# Control_module.net
KiCad netlist of a schematic drawn in EAGLE
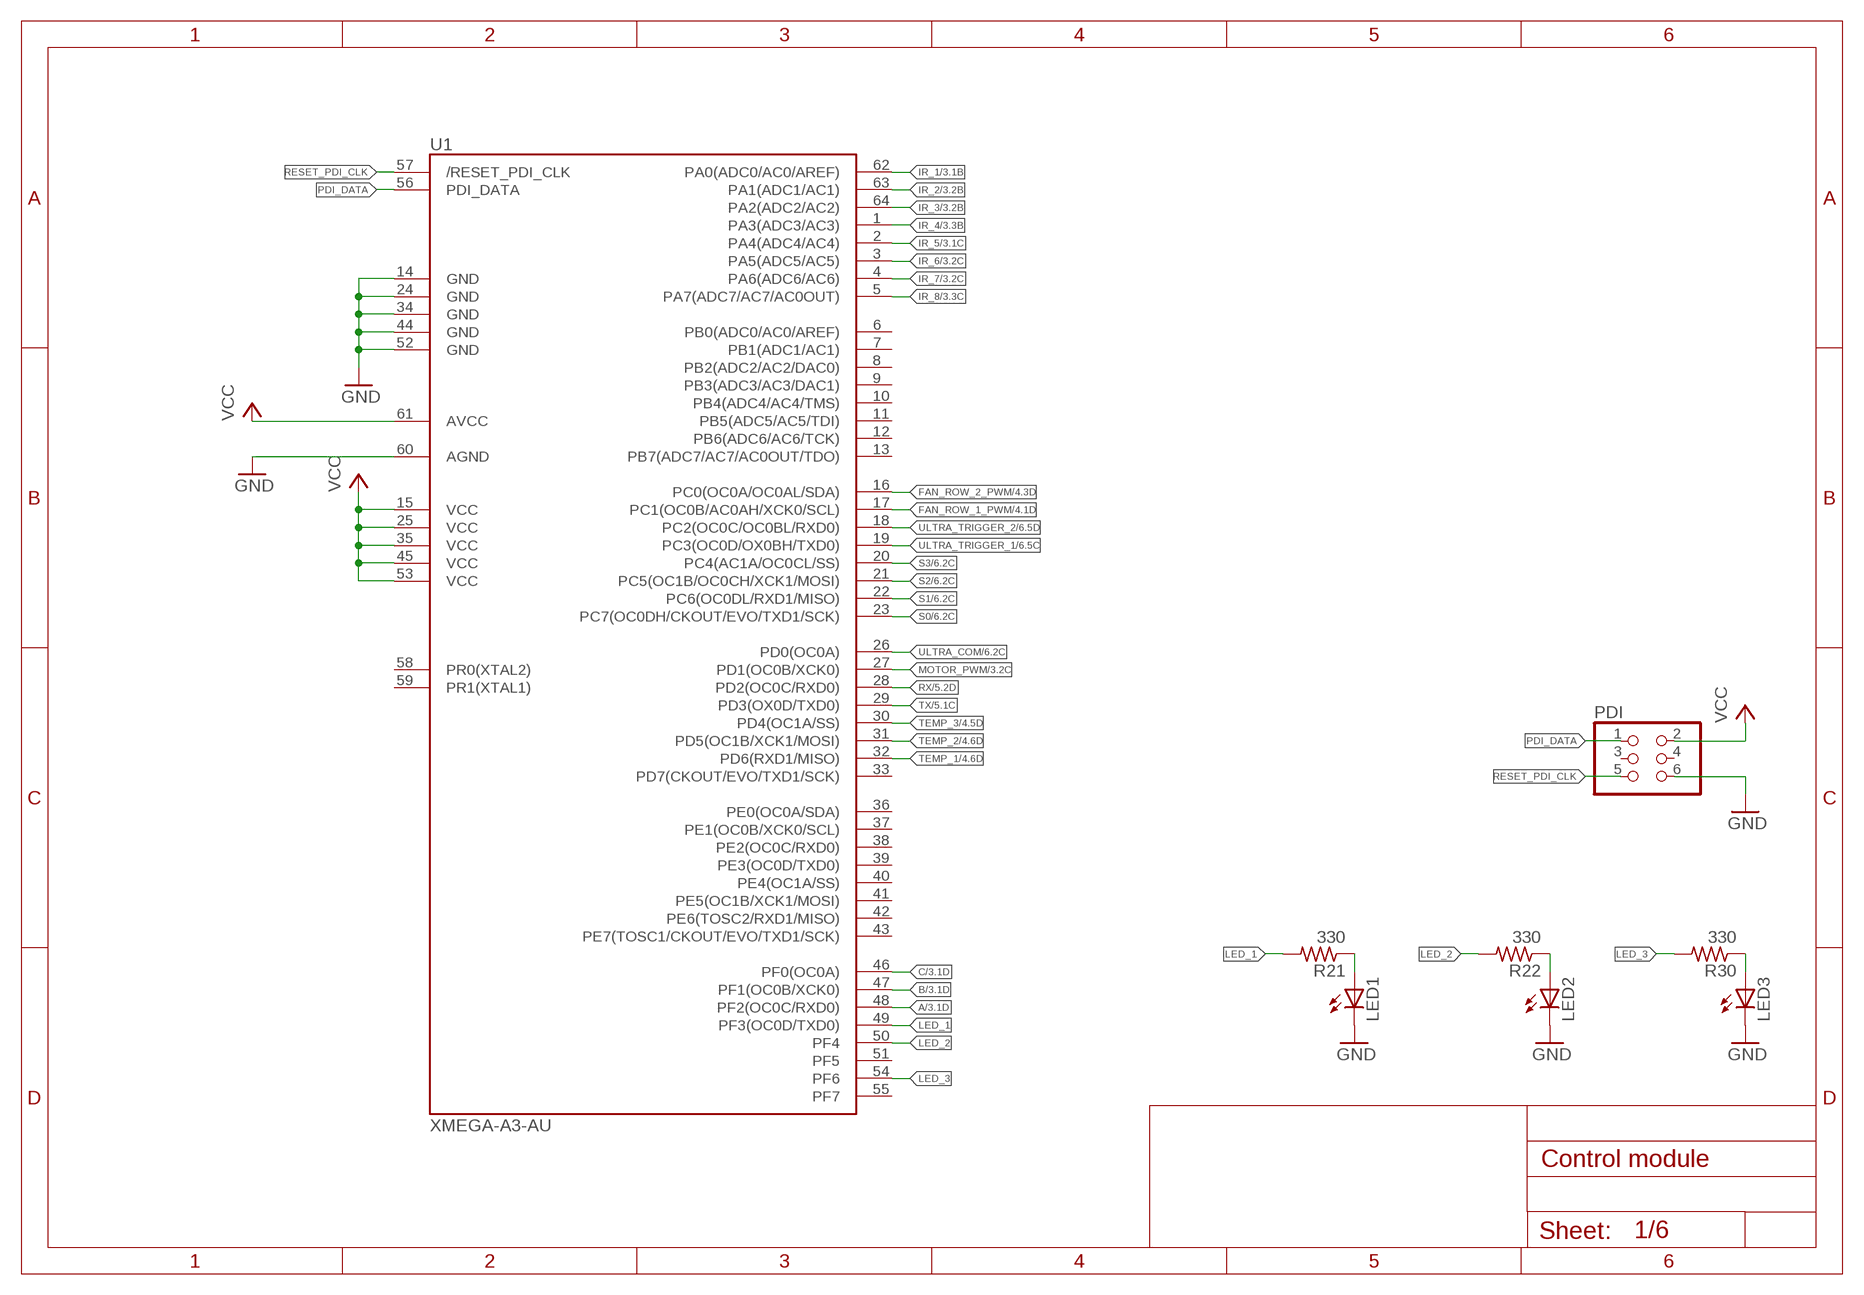
[diagram p0: schematic, sheet 1]
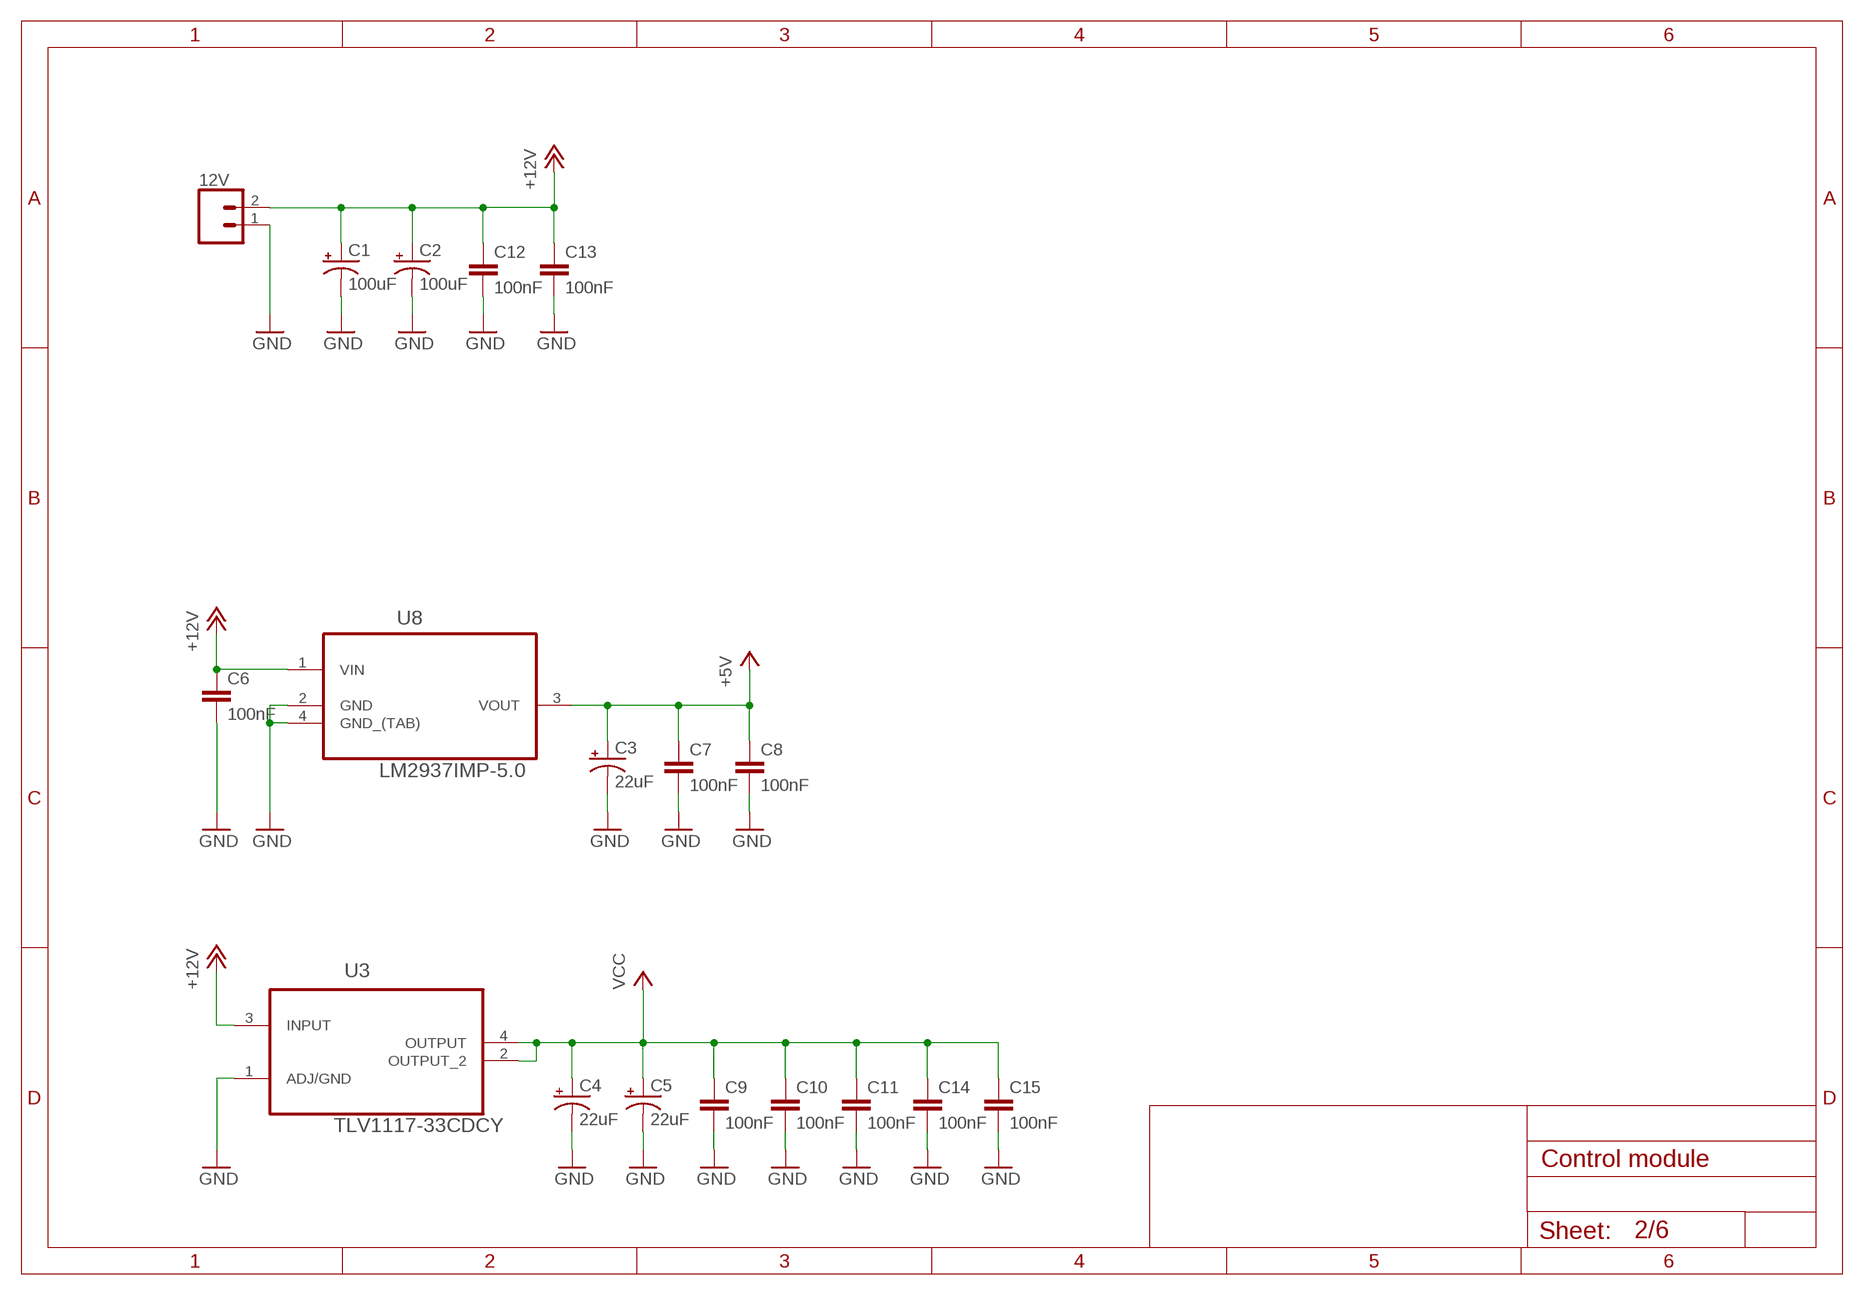
[diagram p1: schematic, sheet 2]
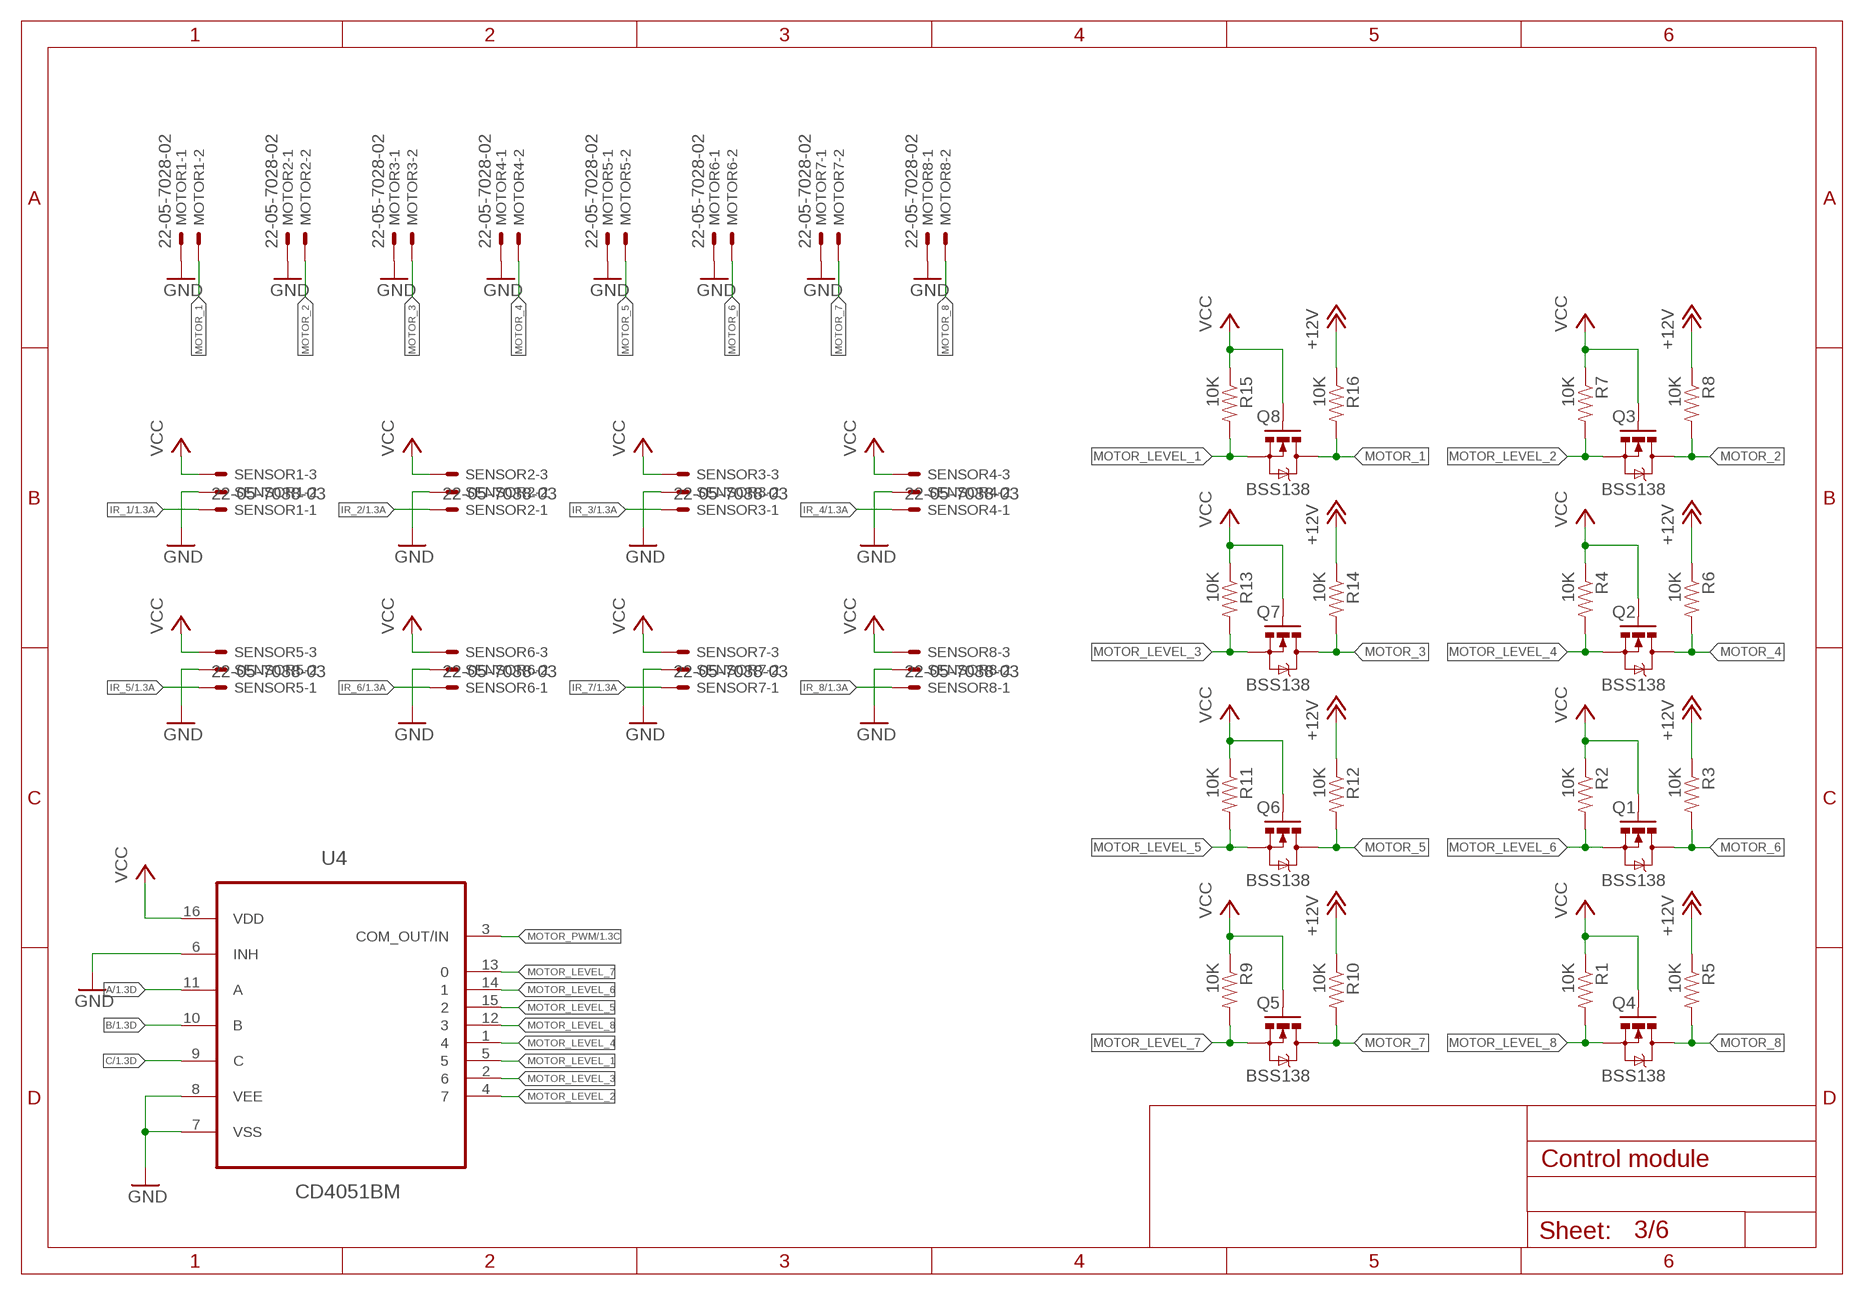
[diagram p2: schematic, sheet 3]
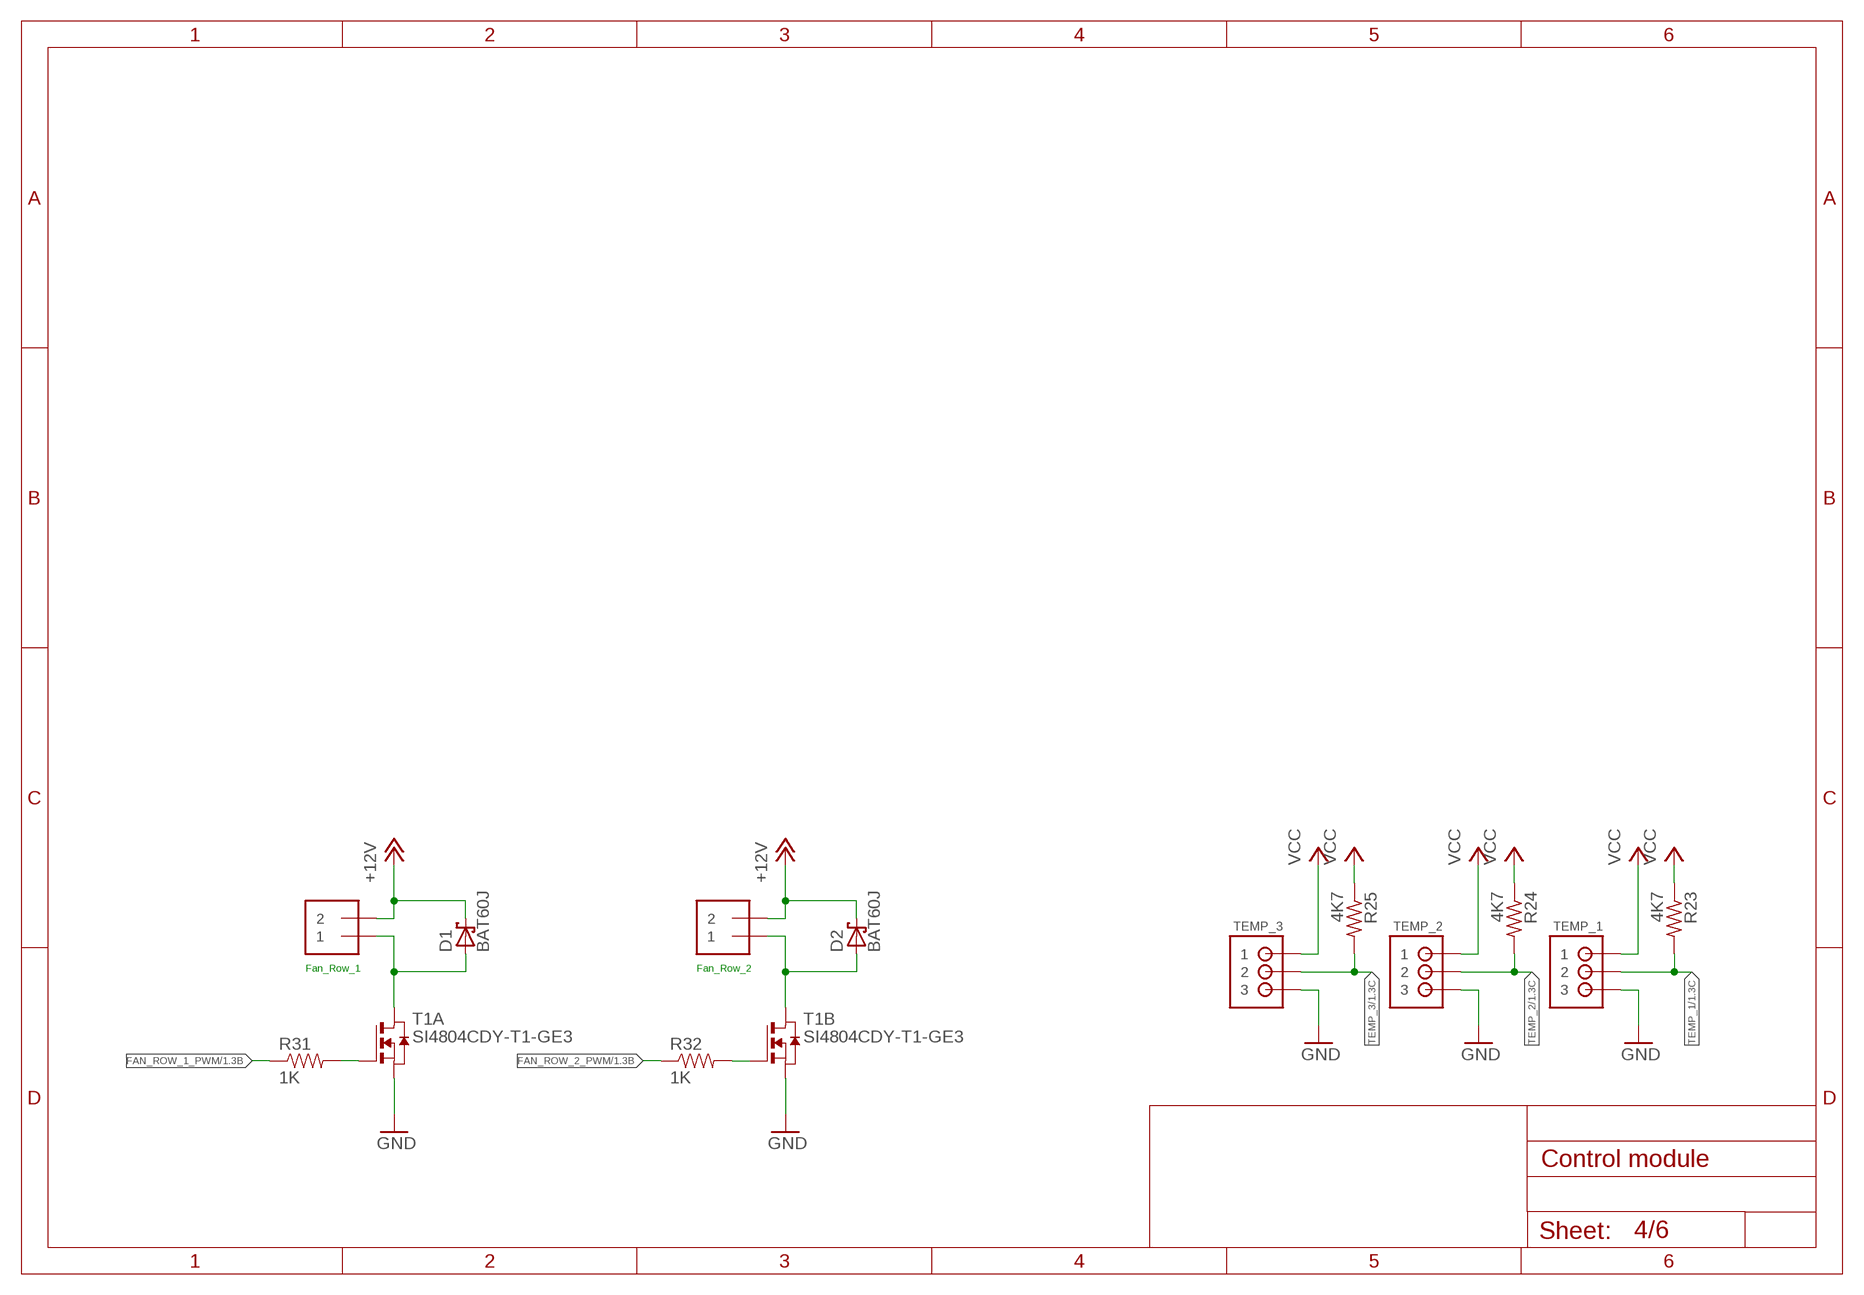
[diagram p3: schematic, sheet 4]
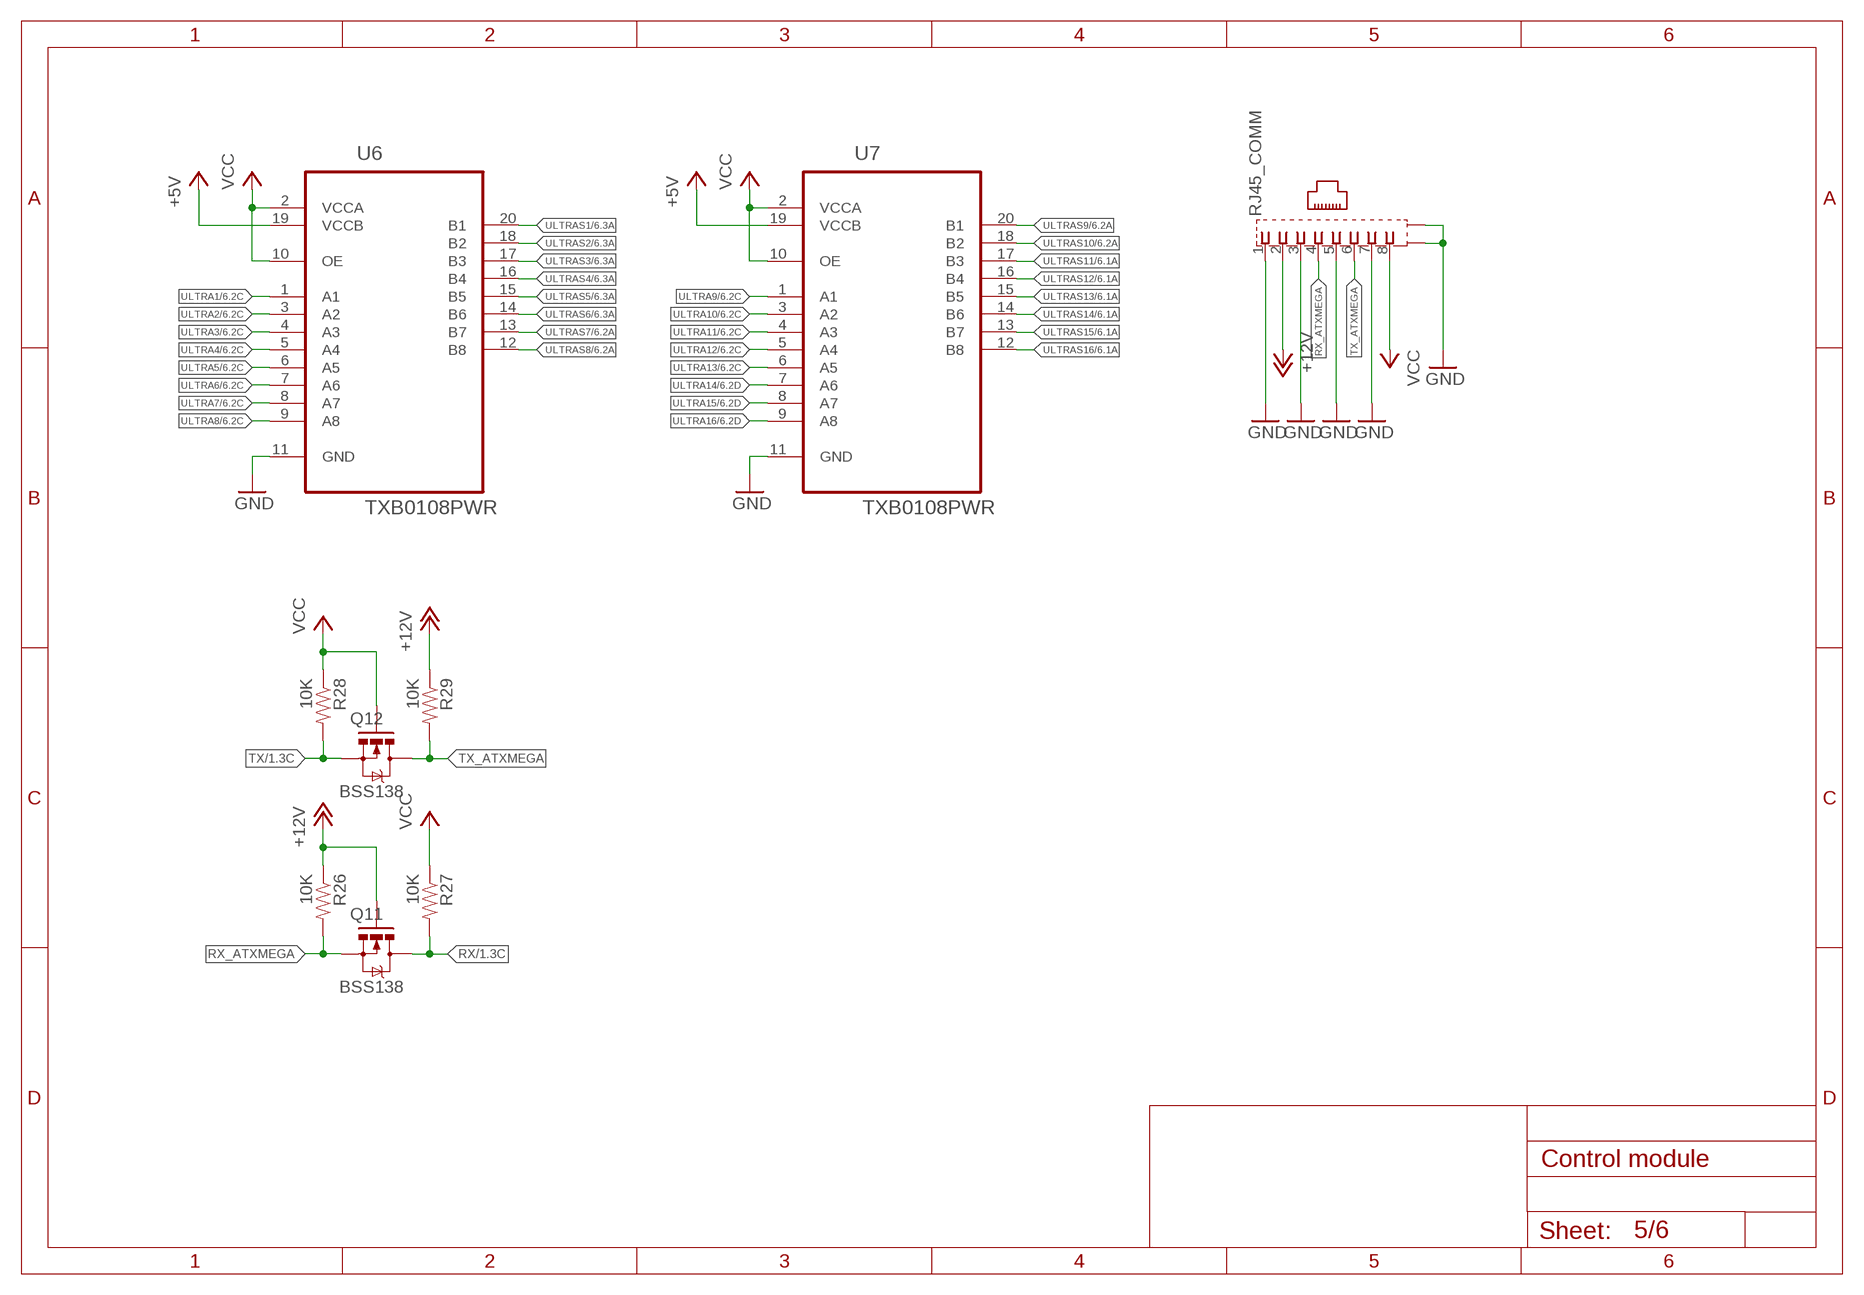
[diagram p4: schematic, sheet 5]
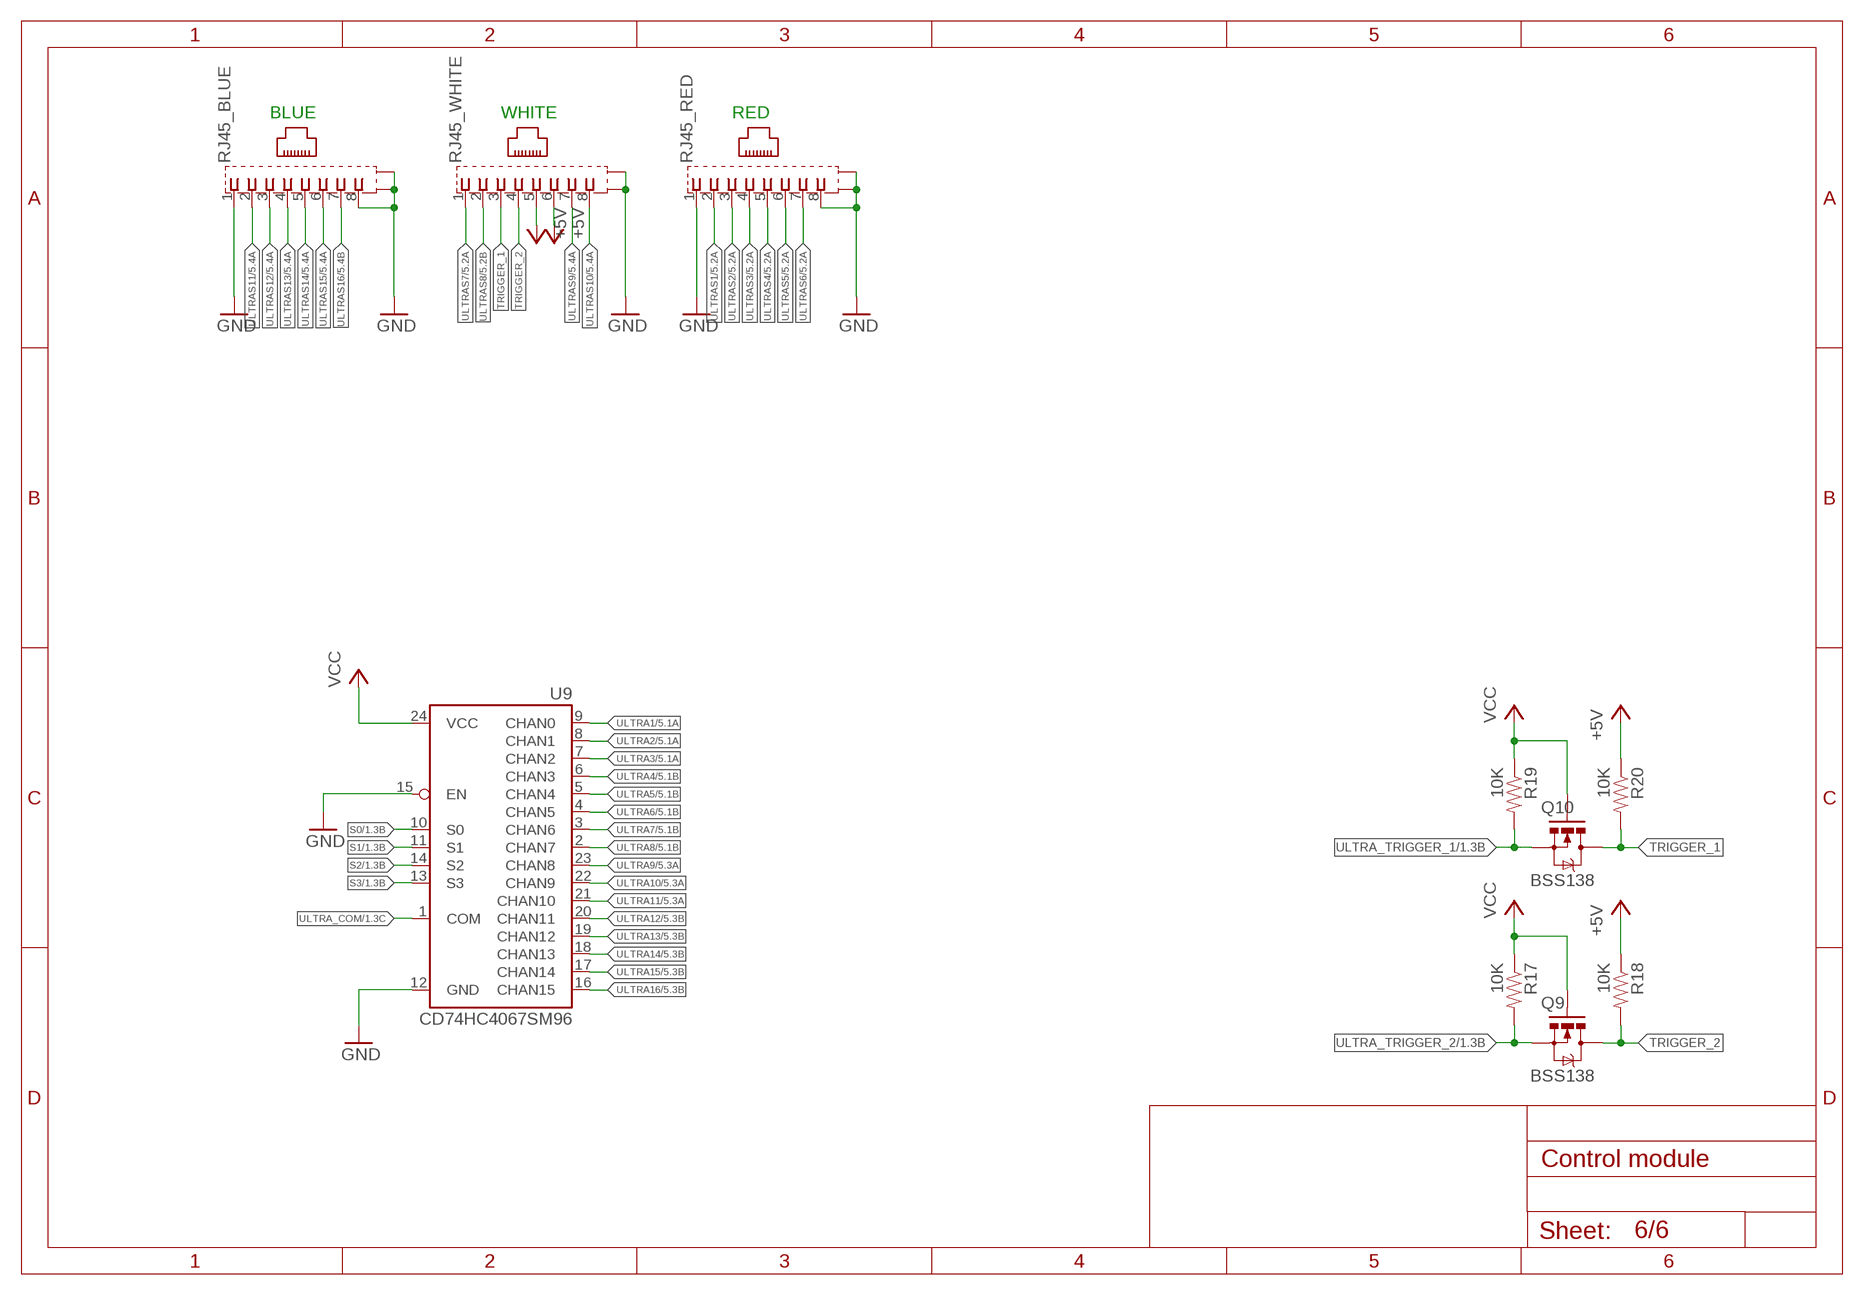
[diagram p5: schematic, sheet 6]

(export (version "E")
  (design (tool "Eeschema 10.0.6"))
  (components
    (comp (ref "MOTOR1")
      (value "22-05-7028-02")
      (footprint "eagle-import:7395-02")
      (fields (field (name "MF") "MOLEX"))
      (libsource (lib "eagle-import") (part "22-?-0205-7028"))
    )
    (comp (ref "MOTOR2")
      (value "22-05-7028-02")
      (footprint "eagle-import:7395-02")
      (fields (field (name "MF") "MOLEX"))
      (libsource (lib "eagle-import") (part "22-?-0205-7028"))
    )
    (comp (ref "MOTOR3")
      (value "22-05-7028-02")
      (footprint "eagle-import:7395-02")
      (fields (field (name "MF") "MOLEX"))
      (libsource (lib "eagle-import") (part "22-?-0205-7028"))
    )
    (comp (ref "MOTOR4")
      (value "22-05-7028-02")
      (footprint "eagle-import:7395-02")
      (fields (field (name "MF") "MOLEX"))
      (libsource (lib "eagle-import") (part "22-?-0205-7028"))
    )
    (comp (ref "MOTOR5")
      (value "22-05-7028-02")
      (footprint "eagle-import:7395-02")
      (fields (field (name "MF") "MOLEX"))
      (libsource (lib "eagle-import") (part "22-?-0205-7028"))
    )
    (comp (ref "MOTOR6")
      (value "22-05-7028-02")
      (footprint "eagle-import:7395-02")
      (fields (field (name "MF") "MOLEX"))
      (libsource (lib "eagle-import") (part "22-?-0205-7028"))
    )
    (comp (ref "MOTOR7")
      (value "22-05-7028-02")
      (footprint "eagle-import:7395-02")
      (fields (field (name "MF") "MOLEX"))
      (libsource (lib "eagle-import") (part "22-?-0205-7028"))
    )
    (comp (ref "MOTOR8")
      (value "22-05-7028-02")
      (footprint "eagle-import:7395-02")
      (fields (field (name "MF") "MOLEX"))
      (libsource (lib "eagle-import") (part "22-?-0205-7028"))
    )
    (comp (ref "Q1")
      (value "BSS138")
      (footprint "eagle-import:SOT23-3")
      (libsource (lib "eagle-import") (part "MOSFET-NCHANNELSMD"))
    )
    (comp (ref "Q2")
      (value "BSS138")
      (footprint "eagle-import:SOT23-3")
      (libsource (lib "eagle-import") (part "MOSFET-NCHANNELSMD"))
    )
    (comp (ref "Q3")
      (value "BSS138")
      (footprint "eagle-import:SOT23-3")
      (libsource (lib "eagle-import") (part "MOSFET-NCHANNELSMD"))
    )
    (comp (ref "Q4")
      (value "BSS138")
      (footprint "eagle-import:SOT23-3")
      (libsource (lib "eagle-import") (part "MOSFET-NCHANNELSMD"))
    )
    (comp (ref "Q5")
      (value "BSS138")
      (footprint "eagle-import:SOT23-3")
      (libsource (lib "eagle-import") (part "MOSFET-NCHANNELSMD"))
    )
    (comp (ref "Q6")
      (value "BSS138")
      (footprint "eagle-import:SOT23-3")
      (libsource (lib "eagle-import") (part "MOSFET-NCHANNELSMD"))
    )
    (comp (ref "Q7")
      (value "BSS138")
      (footprint "eagle-import:SOT23-3")
      (libsource (lib "eagle-import") (part "MOSFET-NCHANNELSMD"))
    )
    (comp (ref "Q8")
      (value "BSS138")
      (footprint "eagle-import:SOT23-3")
      (libsource (lib "eagle-import") (part "MOSFET-NCHANNELSMD"))
    )
    (comp (ref "R1")
      (value "10K")
      (footprint "eagle-import:0603-RES")
      (libsource (lib "eagle-import") (part "RESISTOR0603-RES"))
    )
    (comp (ref "R2")
      (value "10K")
      (footprint "eagle-import:0603-RES")
      (libsource (lib "eagle-import") (part "RESISTOR0603-RES"))
    )
    (comp (ref "R3")
      (value "10K")
      (footprint "eagle-import:0603-RES")
      (libsource (lib "eagle-import") (part "RESISTOR0603-RES"))
    )
    (comp (ref "R4")
      (value "10K")
      (footprint "eagle-import:0603-RES")
      (libsource (lib "eagle-import") (part "RESISTOR0603-RES"))
    )
    (comp (ref "R5")
      (value "10K")
      (footprint "eagle-import:0603-RES")
      (libsource (lib "eagle-import") (part "RESISTOR0603-RES"))
    )
    (comp (ref "R6")
      (value "10K")
      (footprint "eagle-import:0603-RES")
      (libsource (lib "eagle-import") (part "RESISTOR0603-RES"))
    )
    (comp (ref "R7")
      (value "10K")
      (footprint "eagle-import:0603-RES")
      (libsource (lib "eagle-import") (part "RESISTOR0603-RES"))
    )
    (comp (ref "R8")
      (value "10K")
      (footprint "eagle-import:0603-RES")
      (libsource (lib "eagle-import") (part "RESISTOR0603-RES"))
    )
    (comp (ref "R9")
      (value "10K")
      (footprint "eagle-import:0603-RES")
      (libsource (lib "eagle-import") (part "RESISTOR0603-RES"))
    )
    (comp (ref "R10")
      (value "10K")
      (footprint "eagle-import:0603-RES")
      (libsource (lib "eagle-import") (part "RESISTOR0603-RES"))
    )
    (comp (ref "R11")
      (value "10K")
      (footprint "eagle-import:0603-RES")
      (libsource (lib "eagle-import") (part "RESISTOR0603-RES"))
    )
    (comp (ref "R12")
      (value "10K")
      (footprint "eagle-import:0603-RES")
      (libsource (lib "eagle-import") (part "RESISTOR0603-RES"))
    )
    (comp (ref "R13")
      (value "10K")
      (footprint "eagle-import:0603-RES")
      (libsource (lib "eagle-import") (part "RESISTOR0603-RES"))
    )
    (comp (ref "R14")
      (value "10K")
      (footprint "eagle-import:0603-RES")
      (libsource (lib "eagle-import") (part "RESISTOR0603-RES"))
    )
    (comp (ref "R15")
      (value "10K")
      (footprint "eagle-import:0603-RES")
      (libsource (lib "eagle-import") (part "RESISTOR0603-RES"))
    )
    (comp (ref "R16")
      (value "10K")
      (footprint "eagle-import:0603-RES")
      (libsource (lib "eagle-import") (part "RESISTOR0603-RES"))
    )
    (comp (ref "SENSOR1")
      (value "22-05-7038-03")
      (footprint "eagle-import:7395-03")
      (fields (field (name "MF") "MOLEX"))
      (libsource (lib "eagle-import") (part "22-?-0305-7038"))
    )
    (comp (ref "SENSOR2")
      (value "22-05-7038-03")
      (footprint "eagle-import:7395-03")
      (fields (field (name "MF") "MOLEX"))
      (libsource (lib "eagle-import") (part "22-?-0305-7038"))
    )
    (comp (ref "SENSOR3")
      (value "22-05-7038-03")
      (footprint "eagle-import:7395-03")
      (fields (field (name "MF") "MOLEX"))
      (libsource (lib "eagle-import") (part "22-?-0305-7038"))
    )
    (comp (ref "SENSOR4")
      (value "22-05-7038-03")
      (footprint "eagle-import:7395-03")
      (fields (field (name "MF") "MOLEX"))
      (libsource (lib "eagle-import") (part "22-?-0305-7038"))
    )
    (comp (ref "SENSOR5")
      (value "22-05-7038-03")
      (footprint "eagle-import:7395-03")
      (fields (field (name "MF") "MOLEX"))
      (libsource (lib "eagle-import") (part "22-?-0305-7038"))
    )
    (comp (ref "SENSOR6")
      (value "22-05-7038-03")
      (footprint "eagle-import:7395-03")
      (fields (field (name "MF") "MOLEX"))
      (libsource (lib "eagle-import") (part "22-?-0305-7038"))
    )
    (comp (ref "SENSOR7")
      (value "22-05-7038-03")
      (footprint "eagle-import:7395-03")
      (fields (field (name "MF") "MOLEX"))
      (libsource (lib "eagle-import") (part "22-?-0305-7038"))
    )
    (comp (ref "SENSOR8")
      (value "22-05-7038-03")
      (footprint "eagle-import:7395-03")
      (fields (field (name "MF") "MOLEX"))
      (libsource (lib "eagle-import") (part "22-?-0305-7038"))
    )
    (comp (ref "U4")
      (value "CD4051BM")
      (footprint "eagle-import:SOIC127P600X175-16N")
      (libsource (lib "eagle-import") (part "CD4051BM"))
    )
    (comp (ref "LED1")
      (value "LEDCHIPLED_0805")
      (footprint "eagle-import:CHIPLED_0805")
      (libsource (lib "eagle-import") (part "LEDCHIPLED_0805"))
    )
    (comp (ref "LED2")
      (value "LEDCHIPLED_0805")
      (footprint "eagle-import:CHIPLED_0805")
      (libsource (lib "eagle-import") (part "LEDCHIPLED_0805"))
    )
    (comp (ref "LED3")
      (value "LEDCHIPLED_0805")
      (footprint "eagle-import:CHIPLED_0805")
      (libsource (lib "eagle-import") (part "LEDCHIPLED_0805"))
    )
    (comp (ref "PDI")
      (value "PINHD-2X3")
      (footprint "eagle-import:2X03")
      (libsource (lib "eagle-import") (part "PINHD-2X3"))
    )
    (comp (ref "R21")
      (value "330")
      (footprint "eagle-import:R0805")
      (libsource (lib "eagle-import") (part "adafruit_420_R-US_R0805"))
    )
    (comp (ref "R22")
      (value "330")
      (footprint "eagle-import:R0805")
      (libsource (lib "eagle-import") (part "adafruit_420_R-US_R0805"))
    )
    (comp (ref "R30")
      (value "330")
      (footprint "eagle-import:R0805")
      (libsource (lib "eagle-import") (part "adafruit_420_R-US_R0805"))
    )
    (comp (ref "U1")
      (value "XMEGA-A3-AU")
      (footprint "eagle-import:TQFP64_14X14MM_MCU")
      (libsource (lib "eagle-import") (part "XMEGA-A3-AU"))
    )
    (comp (ref "Q9")
      (value "BSS138")
      (footprint "eagle-import:SOT23-3")
      (libsource (lib "eagle-import") (part "MOSFET-NCHANNELSMD"))
    )
    (comp (ref "Q10")
      (value "BSS138")
      (footprint "eagle-import:SOT23-3")
      (libsource (lib "eagle-import") (part "MOSFET-NCHANNELSMD"))
    )
    (comp (ref "R17")
      (value "10K")
      (footprint "eagle-import:0603-RES")
      (libsource (lib "eagle-import") (part "RESISTOR0603-RES"))
    )
    (comp (ref "R18")
      (value "10K")
      (footprint "eagle-import:0603-RES")
      (libsource (lib "eagle-import") (part "RESISTOR0603-RES"))
    )
    (comp (ref "R19")
      (value "10K")
      (footprint "eagle-import:0603-RES")
      (libsource (lib "eagle-import") (part "RESISTOR0603-RES"))
    )
    (comp (ref "R20")
      (value "10K")
      (footprint "eagle-import:0603-RES")
      (libsource (lib "eagle-import") (part "RESISTOR0603-RES"))
    )
    (comp (ref "RJ45_BLUE")
      (value "0446200002")
      (footprint "eagle-import:0446200002")
      (fields (field (name "MF") "MOLEX"))
      (libsource (lib "eagle-import") (part "0446200002"))
    )
    (comp (ref "RJ45_RED")
      (value "0446200002")
      (footprint "eagle-import:0446200002")
      (fields (field (name "MF") "MOLEX"))
      (libsource (lib "eagle-import") (part "0446200002"))
    )
    (comp (ref "RJ45_WHITE")
      (value "0446200002")
      (footprint "eagle-import:0446200002")
      (fields (field (name "MF") "MOLEX"))
      (libsource (lib "eagle-import") (part "0446200002"))
    )
    (comp (ref "U9")
      (value "CD74HC4067SM96")
      (footprint "eagle-import:SSOP24")
      (libsource (lib "eagle-import") (part "744067SM96HC"))
    )
    (comp (ref "D1")
      (value "BAT60J")
      (footprint "eagle-import:SOD323_ST")
      (libsource (lib "eagle-import") (part "BAT60J"))
    )
    (comp (ref "D2")
      (value "BAT60J")
      (footprint "eagle-import:SOD323_ST")
      (libsource (lib "eagle-import") (part "BAT60J"))
    )
    (comp (ref "FAN_1")
      (value "1X2-3.5MM")
      (footprint "eagle-import:1X2-3.5MM")
      (libsource (lib "eagle-import") (part "1X2-3.5MM"))
    )
    (comp (ref "FAN_2")
      (value "1X2-3.5MM")
      (footprint "eagle-import:1X2-3.5MM")
      (libsource (lib "eagle-import") (part "1X2-3.5MM"))
    )
    (comp (ref "R23")
      (value "4K7")
      (footprint "eagle-import:R0805")
      (libsource (lib "eagle-import") (part "R-US_R0805"))
    )
    (comp (ref "R24")
      (value "4K7")
      (footprint "eagle-import:R0805")
      (libsource (lib "eagle-import") (part "R-US_R0805"))
    )
    (comp (ref "R25")
      (value "4K7")
      (footprint "eagle-import:R0805")
      (libsource (lib "eagle-import") (part "R-US_R0805"))
    )
    (comp (ref "R31")
      (value "1K")
      (footprint "eagle-import:0603-RES")
      (libsource (lib "eagle-import") (part "RESISTOR0603-RES"))
    )
    (comp (ref "R32")
      (value "1K")
      (footprint "eagle-import:0603-RES")
      (libsource (lib "eagle-import") (part "RESISTOR0603-RES"))
    )
    (comp (ref "T1")
      (value "SI4804CDY-T1-GE3")
      (footprint "eagle-import:SO8")
      (libsource (lib "eagle-import") (part "DMN3024LSD"))
    )
    (comp (ref "TEMP_1")
      (value "JST-PH_3-PIN_HEADER")
      (footprint "eagle-import:JST_B3B-PH_HEADER")
      (libsource (lib "eagle-import") (part "JST-PH_3-PIN_HEADER"))
    )
    (comp (ref "TEMP_2")
      (value "JST-PH_3-PIN_HEADER")
      (footprint "eagle-import:JST_B3B-PH_HEADER")
      (libsource (lib "eagle-import") (part "JST-PH_3-PIN_HEADER"))
    )
    (comp (ref "TEMP_3")
      (value "JST-PH_3-PIN_HEADER")
      (footprint "eagle-import:JST_B3B-PH_HEADER")
      (libsource (lib "eagle-import") (part "JST-PH_3-PIN_HEADER"))
    )
    (comp (ref "Q11")
      (value "BSS138")
      (footprint "eagle-import:SOT23-3")
      (libsource (lib "eagle-import") (part "MOSFET-NCHANNELSMD"))
    )
    (comp (ref "Q12")
      (value "BSS138")
      (footprint "eagle-import:SOT23-3")
      (libsource (lib "eagle-import") (part "MOSFET-NCHANNELSMD"))
    )
    (comp (ref "R26")
      (value "10K")
      (footprint "eagle-import:0603-RES")
      (libsource (lib "eagle-import") (part "RESISTOR0603-RES"))
    )
    (comp (ref "R27")
      (value "10K")
      (footprint "eagle-import:0603-RES")
      (libsource (lib "eagle-import") (part "RESISTOR0603-RES"))
    )
    (comp (ref "R28")
      (value "10K")
      (footprint "eagle-import:0603-RES")
      (libsource (lib "eagle-import") (part "RESISTOR0603-RES"))
    )
    (comp (ref "R29")
      (value "10K")
      (footprint "eagle-import:0603-RES")
      (libsource (lib "eagle-import") (part "RESISTOR0603-RES"))
    )
    (comp (ref "RJ45_COMM")
      (value "0446200002")
      (footprint "eagle-import:0446200002")
      (fields (field (name "MF") "MOLEX"))
      (libsource (lib "eagle-import") (part "0446200002"))
    )
    (comp (ref "U6")
      (value "TXB0108PWR")
      (footprint "eagle-import:SOP65P640X120-20N")
      (libsource (lib "eagle-import") (part "TXB0108PWR"))
    )
    (comp (ref "U7")
      (value "TXB0108PWR")
      (footprint "eagle-import:SOP65P640X120-20N")
      (libsource (lib "eagle-import") (part "TXB0108PWR"))
    )
    (comp (ref "12V")
      (value "CONN_025MM")
      (footprint "eagle-import:SCREWTERMINAL-5MM-2")
      (libsource (lib "eagle-import") (part "CONN_025MM"))
    )
    (comp (ref "C1")
      (value "100uF")
      (footprint "eagle-import:150CLZ-0810")
      (libsource (lib "eagle-import") (part "CPOL-US150CLZ-0810"))
    )
    (comp (ref "C2")
      (value "100uF")
      (footprint "eagle-import:150CLZ-0810")
      (libsource (lib "eagle-import") (part "CPOL-US150CLZ-0810"))
    )
    (comp (ref "C3")
      (value "22uF")
      (footprint "eagle-import:153CLV-0505")
      (libsource (lib "eagle-import") (part "CPOL-US153CLV-0505"))
    )
    (comp (ref "C4")
      (value "22uF")
      (footprint "eagle-import:153CLV-0505")
      (libsource (lib "eagle-import") (part "CPOL-US153CLV-0505"))
    )
    (comp (ref "C5")
      (value "22uF")
      (footprint "eagle-import:153CLV-0505")
      (libsource (lib "eagle-import") (part "CPOL-US153CLV-0505"))
    )
    (comp (ref "C6")
      (value "100nF")
      (footprint "eagle-import:0805")
      (libsource (lib "eagle-import") (part "1.0UF-0805-25V-(+80/-20%)"))
    )
    (comp (ref "C7")
      (value "100nF")
      (footprint "eagle-import:0805")
      (libsource (lib "eagle-import") (part "1.0UF-0805-25V-(+80/-20%)"))
    )
    (comp (ref "C8")
      (value "100nF")
      (footprint "eagle-import:0805")
      (libsource (lib "eagle-import") (part "1.0UF-0805-25V-(+80/-20%)"))
    )
    (comp (ref "C9")
      (value "100nF")
      (footprint "eagle-import:0805")
      (libsource (lib "eagle-import") (part "1.0UF-0805-25V-(+80/-20%)"))
    )
    (comp (ref "C10")
      (value "100nF")
      (footprint "eagle-import:0805")
      (libsource (lib "eagle-import") (part "1.0UF-0805-25V-(+80/-20%)"))
    )
    (comp (ref "C11")
      (value "100nF")
      (footprint "eagle-import:0805")
      (libsource (lib "eagle-import") (part "1.0UF-0805-25V-(+80/-20%)"))
    )
    (comp (ref "C12")
      (value "100nF")
      (footprint "eagle-import:0805")
      (libsource (lib "eagle-import") (part "1.0UF-0805-25V-(+80/-20%)"))
    )
    (comp (ref "C13")
      (value "100nF")
      (footprint "eagle-import:0805")
      (libsource (lib "eagle-import") (part "1.0UF-0805-25V-(+80/-20%)"))
    )
    (comp (ref "C14")
      (value "100nF")
      (footprint "eagle-import:0805")
      (libsource (lib "eagle-import") (part "1.0UF-0805-25V-(+80/-20%)"))
    )
    (comp (ref "C15")
      (value "100nF")
      (footprint "eagle-import:0805")
      (libsource (lib "eagle-import") (part "1.0UF-0805-25V-(+80/-20%)"))
    )
    (comp (ref "U3")
      (value "TLV1117-33CDCY")
      (footprint "eagle-import:SOT230P700X180-4N")
      (libsource (lib "eagle-import") (part "TLV1117-33CDCY"))
    )
    (comp (ref "U8")
      (value "LM2937IMP-5.0")
      (footprint "eagle-import:SOT230P700X180-4N")
      (libsource (lib "eagle-import") (part "LM2937IMP-5.0"))
    )
  )
  (nets
    (net (code "1") (name "+5V") (class "Default")
      (node (ref "C3") (pin "+") (pinfunction "+_+") (pintype "passive"))
      (node (ref "C7") (pin "1") (pinfunction "1_1") (pintype "passive"))
      (node (ref "C8") (pin "1") (pinfunction "1_1") (pintype "passive"))
      (node (ref "R18") (pin "1") (pinfunction "1_1") (pintype "passive"))
      (node (ref "R20") (pin "1") (pinfunction "1_1") (pintype "passive"))
      (node (ref "RJ45_WHITE") (pin "5") (pinfunction "5_5") (pintype "passive"))
      (node (ref "RJ45_WHITE") (pin "6") (pinfunction "6_6") (pintype "passive"))
      (node (ref "U6") (pin "19") (pinfunction "VCCB_19") (pintype "power_in"))
      (node (ref "U7") (pin "19") (pinfunction "VCCB_19") (pintype "power_in"))
      (node (ref "U8") (pin "3") (pinfunction "VOUT_3") (pintype "output"))
    )
    (net (code "2") (name "+12V") (class "Default")
      (node (ref "12V") (pin "2") (pinfunction "2_2") (pintype "passive"))
      (node (ref "C1") (pin "+") (pinfunction "+_+") (pintype "passive"))
      (node (ref "C12") (pin "1") (pinfunction "1_1") (pintype "passive"))
      (node (ref "C13") (pin "1") (pinfunction "1_1") (pintype "passive"))
      (node (ref "C2") (pin "+") (pinfunction "+_+") (pintype "passive"))
      (node (ref "C6") (pin "1") (pinfunction "1_1") (pintype "passive"))
      (node (ref "D1") (pin "C") (pinfunction "C_C") (pintype "passive"))
      (node (ref "D2") (pin "C") (pinfunction "C_C") (pintype "passive"))
      (node (ref "FAN_1") (pin "2") (pinfunction "2_2") (pintype "passive"))
      (node (ref "FAN_2") (pin "2") (pinfunction "2_2") (pintype "passive"))
      (node (ref "Q11") (pin "1") (pinfunction "G_1") (pintype "passive"))
      (node (ref "R10") (pin "1") (pinfunction "1_1") (pintype "passive"))
      (node (ref "R12") (pin "1") (pinfunction "1_1") (pintype "passive"))
      (node (ref "R14") (pin "1") (pinfunction "1_1") (pintype "passive"))
      (node (ref "R16") (pin "1") (pinfunction "1_1") (pintype "passive"))
      (node (ref "R26") (pin "1") (pinfunction "1_1") (pintype "passive"))
      (node (ref "R29") (pin "1") (pinfunction "1_1") (pintype "passive"))
      (node (ref "R3") (pin "1") (pinfunction "1_1") (pintype "passive"))
      (node (ref "R5") (pin "1") (pinfunction "1_1") (pintype "passive"))
      (node (ref "R6") (pin "1") (pinfunction "1_1") (pintype "passive"))
      (node (ref "R8") (pin "1") (pinfunction "1_1") (pintype "passive"))
      (node (ref "RJ45_COMM") (pin "2") (pinfunction "2_2") (pintype "passive"))
      (node (ref "U3") (pin "3") (pinfunction "INPUT_3") (pintype "input"))
      (node (ref "U8") (pin "1") (pinfunction "VIN_1") (pintype "input"))
    )
    (net (code "3") (name "A") (class "Default")
      (node (ref "U1") (pin "48") (pinfunction "PF2(OC0C/RXD0)_48") (pintype "bidirectional"))
      (node (ref "U4") (pin "11") (pinfunction "A_11") (pintype "input"))
    )
    (net (code "4") (name "B") (class "Default")
      (node (ref "U1") (pin "47") (pinfunction "PF1(OC0B/XCK0)_47") (pintype "bidirectional"))
      (node (ref "U4") (pin "10") (pinfunction "B_10") (pintype "input"))
    )
    (net (code "5") (name "C") (class "Default")
      (node (ref "U1") (pin "46") (pinfunction "PF0(OC0A)_46") (pintype "bidirectional"))
      (node (ref "U4") (pin "9") (pinfunction "C_9") (pintype "bidirectional"))
    )
    (net (code "6") (name "FAN_ROW_1_PWM") (class "Default")
      (node (ref "R31") (pin "1") (pinfunction "1_1") (pintype "passive"))
      (node (ref "U1") (pin "17") (pinfunction "PC1(OC0B/AC0AH/XCK0/SCL)_17") (pintype "bidirectional"))
    )
    (net (code "7") (name "FAN_ROW_2_PWM") (class "Default")
      (node (ref "R32") (pin "1") (pinfunction "1_1") (pintype "passive"))
      (node (ref "U1") (pin "16") (pinfunction "PC0(OC0A/OC0AL/SDA)_16") (pintype "bidirectional"))
    )
    (net (code "8") (name "GND") (class "Default")
      (node (ref "12V") (pin "1") (pinfunction "1_1") (pintype "passive"))
      (node (ref "C1") (pin "-") (pinfunction "-_-") (pintype "passive"))
      (node (ref "C10") (pin "2") (pinfunction "2_2") (pintype "passive"))
      (node (ref "C11") (pin "2") (pinfunction "2_2") (pintype "passive"))
      (node (ref "C12") (pin "2") (pinfunction "2_2") (pintype "passive"))
      (node (ref "C13") (pin "2") (pinfunction "2_2") (pintype "passive"))
      (node (ref "C14") (pin "2") (pinfunction "2_2") (pintype "passive"))
      (node (ref "C15") (pin "2") (pinfunction "2_2") (pintype "passive"))
      (node (ref "C2") (pin "-") (pinfunction "-_-") (pintype "passive"))
      (node (ref "C3") (pin "-") (pinfunction "-_-") (pintype "passive"))
      (node (ref "C4") (pin "-") (pinfunction "-_-") (pintype "passive"))
      (node (ref "C5") (pin "-") (pinfunction "-_-") (pintype "passive"))
      (node (ref "C6") (pin "2") (pinfunction "2_2") (pintype "passive"))
      (node (ref "C7") (pin "2") (pinfunction "2_2") (pintype "passive"))
      (node (ref "C8") (pin "2") (pinfunction "2_2") (pintype "passive"))
      (node (ref "C9") (pin "2") (pinfunction "2_2") (pintype "passive"))
      (node (ref "LED1") (pin "C") (pinfunction "C_C") (pintype "passive"))
      (node (ref "LED2") (pin "C") (pinfunction "C_C") (pintype "passive"))
      (node (ref "LED3") (pin "C") (pinfunction "C_C") (pintype "passive"))
      (node (ref "MOTOR1") (pin "1") (pinfunction "S_1") (pintype "passive"))
      (node (ref "MOTOR2") (pin "1") (pinfunction "S_1") (pintype "passive"))
      (node (ref "MOTOR3") (pin "1") (pinfunction "S_1") (pintype "passive"))
      (node (ref "MOTOR4") (pin "1") (pinfunction "S_1") (pintype "passive"))
      (node (ref "MOTOR5") (pin "1") (pinfunction "S_1") (pintype "passive"))
      (node (ref "MOTOR6") (pin "1") (pinfunction "S_1") (pintype "passive"))
      (node (ref "MOTOR7") (pin "1") (pinfunction "S_1") (pintype "passive"))
      (node (ref "MOTOR8") (pin "1") (pinfunction "S_1") (pintype "passive"))
      (node (ref "PDI") (pin "6") (pinfunction "6_6") (pintype "passive"))
      (node (ref "RJ45_BLUE") (pin "1") (pinfunction "1_1") (pintype "passive"))
      (node (ref "RJ45_BLUE") (pin "8") (pinfunction "8_8") (pintype "passive"))
      (node (ref "RJ45_BLUE") (pin "S@1") (pinfunction "S1_S@1") (pintype "passive"))
      (node (ref "RJ45_BLUE") (pin "S@2") (pinfunction "S2_S@2") (pintype "passive"))
      (node (ref "RJ45_COMM") (pin "1") (pinfunction "1_1") (pintype "passive"))
      (node (ref "RJ45_COMM") (pin "3") (pinfunction "3_3") (pintype "passive"))
      (node (ref "RJ45_COMM") (pin "5") (pinfunction "5_5") (pintype "passive"))
      (node (ref "RJ45_COMM") (pin "7") (pinfunction "7_7") (pintype "passive"))
      (node (ref "RJ45_COMM") (pin "S@1") (pinfunction "S1_S@1") (pintype "passive"))
      (node (ref "RJ45_COMM") (pin "S@2") (pinfunction "S2_S@2") (pintype "passive"))
      (node (ref "RJ45_RED") (pin "1") (pinfunction "1_1") (pintype "passive"))
      (node (ref "RJ45_RED") (pin "8") (pinfunction "8_8") (pintype "passive"))
      (node (ref "RJ45_RED") (pin "S@1") (pinfunction "S1_S@1") (pintype "passive"))
      (node (ref "RJ45_RED") (pin "S@2") (pinfunction "S2_S@2") (pintype "passive"))
      (node (ref "RJ45_WHITE") (pin "S@1") (pinfunction "S1_S@1") (pintype "passive"))
      (node (ref "RJ45_WHITE") (pin "S@2") (pinfunction "S2_S@2") (pintype "passive"))
      (node (ref "SENSOR1") (pin "2") (pinfunction "S_2") (pintype "passive"))
      (node (ref "SENSOR2") (pin "2") (pinfunction "S_2") (pintype "passive"))
      (node (ref "SENSOR3") (pin "2") (pinfunction "S_2") (pintype "passive"))
      (node (ref "SENSOR4") (pin "2") (pinfunction "S_2") (pintype "passive"))
      (node (ref "SENSOR5") (pin "2") (pinfunction "S_2") (pintype "passive"))
      (node (ref "SENSOR6") (pin "2") (pinfunction "S_2") (pintype "passive"))
      (node (ref "SENSOR7") (pin "2") (pinfunction "S_2") (pintype "passive"))
      (node (ref "SENSOR8") (pin "2") (pinfunction "S_2") (pintype "passive"))
      (node (ref "T1") (pin "1") (pinfunction "S_1") (pintype "passive"))
      (node (ref "T1") (pin "3") (pinfunction "S_3") (pintype "passive"))
      (node (ref "TEMP_1") (pin "P3") (pinfunction "3_P3") (pintype "bidirectional"))
      (node (ref "TEMP_2") (pin "P3") (pinfunction "3_P3") (pintype "bidirectional"))
      (node (ref "TEMP_3") (pin "P3") (pinfunction "3_P3") (pintype "bidirectional"))
      (node (ref "U1") (pin "14") (pinfunction "GND1_14") (pintype "bidirectional"))
      (node (ref "U1") (pin "24") (pinfunction "GND2_24") (pintype "bidirectional"))
      (node (ref "U1") (pin "34") (pinfunction "GND3_34") (pintype "bidirectional"))
      (node (ref "U1") (pin "44") (pinfunction "GND4_44") (pintype "bidirectional"))
      (node (ref "U1") (pin "52") (pinfunction "GND5_52") (pintype "bidirectional"))
      (node (ref "U1") (pin "60") (pinfunction "AGND_60") (pintype "bidirectional"))
      (node (ref "U3") (pin "1") (pinfunction "ADJ/GND_1") (pintype "input"))
      (node (ref "U4") (pin "6") (pinfunction "INH_6") (pintype "input"))
      (node (ref "U4") (pin "7") (pinfunction "VSS_7") (pintype "power_in"))
      (node (ref "U4") (pin "8") (pinfunction "VEE_8") (pintype "power_in"))
      (node (ref "U6") (pin "11") (pinfunction "GND_11") (pintype "passive"))
      (node (ref "U7") (pin "11") (pinfunction "GND_11") (pintype "passive"))
      (node (ref "U8") (pin "2") (pinfunction "GND_2") (pintype "passive"))
      (node (ref "U8") (pin "4") (pinfunction "GND_(TAB)_4") (pintype "passive"))
      (node (ref "U9") (pin "12") (pinfunction "GND_12") (pintype "bidirectional"))
      (node (ref "U9") (pin "15") (pinfunction "EN_15") (pintype "input"))
    )
    (net (code "9") (name "IR_1") (class "Default")
      (node (ref "SENSOR1") (pin "1") (pinfunction "S_1") (pintype "passive"))
      (node (ref "U1") (pin "62") (pinfunction "PA0(ADC0/AC0/AREF)_62") (pintype "bidirectional"))
    )
    (net (code "10") (name "IR_2") (class "Default")
      (node (ref "SENSOR2") (pin "1") (pinfunction "S_1") (pintype "passive"))
      (node (ref "U1") (pin "63") (pinfunction "PA1(ADC1/AC1)_63") (pintype "bidirectional"))
    )
    (net (code "11") (name "IR_3") (class "Default")
      (node (ref "SENSOR3") (pin "1") (pinfunction "S_1") (pintype "passive"))
      (node (ref "U1") (pin "64") (pinfunction "PA2(ADC2/AC2)_64") (pintype "bidirectional"))
    )
    (net (code "12") (name "IR_4") (class "Default")
      (node (ref "SENSOR4") (pin "1") (pinfunction "S_1") (pintype "passive"))
      (node (ref "U1") (pin "1") (pinfunction "PA3(ADC3/AC3)_1") (pintype "bidirectional"))
    )
    (net (code "13") (name "IR_5") (class "Default")
      (node (ref "SENSOR5") (pin "1") (pinfunction "S_1") (pintype "passive"))
      (node (ref "U1") (pin "2") (pinfunction "PA4(ADC4/AC4)_2") (pintype "bidirectional"))
    )
    (net (code "14") (name "IR_6") (class "Default")
      (node (ref "SENSOR6") (pin "1") (pinfunction "S_1") (pintype "passive"))
      (node (ref "U1") (pin "3") (pinfunction "PA5(ADC5/AC5)_3") (pintype "bidirectional"))
    )
    (net (code "15") (name "IR_7") (class "Default")
      (node (ref "SENSOR7") (pin "1") (pinfunction "S_1") (pintype "passive"))
      (node (ref "U1") (pin "4") (pinfunction "PA6(ADC6/AC6)_4") (pintype "bidirectional"))
    )
    (net (code "16") (name "IR_8") (class "Default")
      (node (ref "SENSOR8") (pin "1") (pinfunction "S_1") (pintype "passive"))
      (node (ref "U1") (pin "5") (pinfunction "PA7(ADC7/AC7/AC0OUT)_5") (pintype "bidirectional"))
    )
    (net (code "17") (name "LED_1") (class "Default")
      (node (ref "R21") (pin "2") (pinfunction "2_2") (pintype "passive"))
      (node (ref "U1") (pin "49") (pinfunction "PF3(OC0D/TXD0)_49") (pintype "bidirectional"))
    )
    (net (code "18") (name "LED_2") (class "Default")
      (node (ref "R22") (pin "2") (pinfunction "2_2") (pintype "passive"))
      (node (ref "U1") (pin "50") (pinfunction "PF4_50") (pintype "bidirectional"))
    )
    (net (code "19") (name "LED_3") (class "Default")
      (node (ref "R30") (pin "2") (pinfunction "2_2") (pintype "passive"))
      (node (ref "U1") (pin "54") (pinfunction "PF6_54") (pintype "bidirectional"))
    )
    (net (code "20") (name "MOTOR_1") (class "Default")
      (node (ref "MOTOR1") (pin "2") (pinfunction "S_2") (pintype "passive"))
      (node (ref "Q8") (pin "3") (pinfunction "D_3") (pintype "passive"))
      (node (ref "R16") (pin "2") (pinfunction "2_2") (pintype "passive"))
    )
    (net (code "21") (name "MOTOR_2") (class "Default")
      (node (ref "MOTOR2") (pin "2") (pinfunction "S_2") (pintype "passive"))
      (node (ref "Q3") (pin "3") (pinfunction "D_3") (pintype "passive"))
      (node (ref "R8") (pin "2") (pinfunction "2_2") (pintype "passive"))
    )
    (net (code "22") (name "MOTOR_3") (class "Default")
      (node (ref "MOTOR3") (pin "2") (pinfunction "S_2") (pintype "passive"))
      (node (ref "Q7") (pin "3") (pinfunction "D_3") (pintype "passive"))
      (node (ref "R14") (pin "2") (pinfunction "2_2") (pintype "passive"))
    )
    (net (code "23") (name "MOTOR_4") (class "Default")
      (node (ref "MOTOR4") (pin "2") (pinfunction "S_2") (pintype "passive"))
      (node (ref "Q2") (pin "3") (pinfunction "D_3") (pintype "passive"))
      (node (ref "R6") (pin "2") (pinfunction "2_2") (pintype "passive"))
    )
    (net (code "24") (name "MOTOR_5") (class "Default")
      (node (ref "MOTOR5") (pin "2") (pinfunction "S_2") (pintype "passive"))
      (node (ref "Q6") (pin "3") (pinfunction "D_3") (pintype "passive"))
      (node (ref "R12") (pin "2") (pinfunction "2_2") (pintype "passive"))
    )
    (net (code "25") (name "MOTOR_6") (class "Default")
      (node (ref "MOTOR6") (pin "2") (pinfunction "S_2") (pintype "passive"))
      (node (ref "Q1") (pin "3") (pinfunction "D_3") (pintype "passive"))
      (node (ref "R3") (pin "2") (pinfunction "2_2") (pintype "passive"))
    )
    (net (code "26") (name "MOTOR_7") (class "Default")
      (node (ref "MOTOR7") (pin "2") (pinfunction "S_2") (pintype "passive"))
      (node (ref "Q5") (pin "3") (pinfunction "D_3") (pintype "passive"))
      (node (ref "R10") (pin "2") (pinfunction "2_2") (pintype "passive"))
    )
    (net (code "27") (name "MOTOR_8") (class "Default")
      (node (ref "MOTOR8") (pin "2") (pinfunction "S_2") (pintype "passive"))
      (node (ref "Q4") (pin "3") (pinfunction "D_3") (pintype "passive"))
      (node (ref "R5") (pin "2") (pinfunction "2_2") (pintype "passive"))
    )
    (net (code "28") (name "MOTOR_LEVEL_1") (class "Default")
      (node (ref "Q8") (pin "2") (pinfunction "S_2") (pintype "passive"))
      (node (ref "R15") (pin "2") (pinfunction "2_2") (pintype "passive"))
      (node (ref "U4") (pin "5") (pinfunction "5_5") (pintype "bidirectional"))
    )
    (net (code "29") (name "MOTOR_LEVEL_2") (class "Default")
      (node (ref "Q3") (pin "2") (pinfunction "S_2") (pintype "passive"))
      (node (ref "R7") (pin "2") (pinfunction "2_2") (pintype "passive"))
      (node (ref "U4") (pin "4") (pinfunction "7_4") (pintype "bidirectional"))
    )
    (net (code "30") (name "MOTOR_LEVEL_3") (class "Default")
      (node (ref "Q7") (pin "2") (pinfunction "S_2") (pintype "passive"))
      (node (ref "R13") (pin "2") (pinfunction "2_2") (pintype "passive"))
      (node (ref "U4") (pin "2") (pinfunction "6_2") (pintype "bidirectional"))
    )
    (net (code "31") (name "MOTOR_LEVEL_4") (class "Default")
      (node (ref "Q2") (pin "2") (pinfunction "S_2") (pintype "passive"))
      (node (ref "R4") (pin "2") (pinfunction "2_2") (pintype "passive"))
      (node (ref "U4") (pin "1") (pinfunction "4_1") (pintype "bidirectional"))
    )
    (net (code "32") (name "MOTOR_LEVEL_5") (class "Default")
      (node (ref "Q6") (pin "2") (pinfunction "S_2") (pintype "passive"))
      (node (ref "R11") (pin "2") (pinfunction "2_2") (pintype "passive"))
      (node (ref "U4") (pin "15") (pinfunction "2_15") (pintype "bidirectional"))
    )
    (net (code "33") (name "MOTOR_LEVEL_6") (class "Default")
      (node (ref "Q1") (pin "2") (pinfunction "S_2") (pintype "passive"))
      (node (ref "R2") (pin "2") (pinfunction "2_2") (pintype "passive"))
      (node (ref "U4") (pin "14") (pinfunction "1_14") (pintype "bidirectional"))
    )
    (net (code "34") (name "MOTOR_LEVEL_7") (class "Default")
      (node (ref "Q5") (pin "2") (pinfunction "S_2") (pintype "passive"))
      (node (ref "R9") (pin "2") (pinfunction "2_2") (pintype "passive"))
      (node (ref "U4") (pin "13") (pinfunction "0_13") (pintype "bidirectional"))
    )
    (net (code "35") (name "MOTOR_LEVEL_8") (class "Default")
      (node (ref "Q4") (pin "2") (pinfunction "S_2") (pintype "passive"))
      (node (ref "R1") (pin "2") (pinfunction "2_2") (pintype "passive"))
      (node (ref "U4") (pin "12") (pinfunction "3_12") (pintype "bidirectional"))
    )
    (net (code "36") (name "MOTOR_PWM") (class "Default")
      (node (ref "U1") (pin "27") (pinfunction "PD1(OC0B/XCK0)_27") (pintype "bidirectional"))
      (node (ref "U4") (pin "3") (pinfunction "COM_OUT/IN_3") (pintype "bidirectional"))
    )
    (net (code "37") (name "Net-(D1-PadA)") (class "Default")
      (node (ref "D1") (pin "A") (pinfunction "A_A") (pintype "passive"))
      (node (ref "FAN_1") (pin "1") (pinfunction "1_1") (pintype "passive"))
      (node (ref "T1") (pin "7") (pinfunction "D_7") (pintype "passive"))
      (node (ref "T1") (pin "8") (pinfunction "D_8") (pintype "passive"))
    )
    (net (code "38") (name "Net-(D2-PadA)") (class "Default")
      (node (ref "D2") (pin "A") (pinfunction "A_A") (pintype "passive"))
      (node (ref "FAN_2") (pin "1") (pinfunction "1_1") (pintype "passive"))
      (node (ref "T1") (pin "5") (pinfunction "D_5") (pintype "passive"))
      (node (ref "T1") (pin "6") (pinfunction "D_6") (pintype "passive"))
    )
    (net (code "39") (name "Net-(LED1-PadA)") (class "Default")
      (node (ref "LED1") (pin "A") (pinfunction "A_A") (pintype "passive"))
      (node (ref "R21") (pin "1") (pinfunction "1_1") (pintype "passive"))
    )
    (net (code "40") (name "Net-(LED2-PadA)") (class "Default")
      (node (ref "LED2") (pin "A") (pinfunction "A_A") (pintype "passive"))
      (node (ref "R22") (pin "1") (pinfunction "1_1") (pintype "passive"))
    )
    (net (code "41") (name "Net-(LED3-PadA)") (class "Default")
      (node (ref "LED3") (pin "A") (pinfunction "A_A") (pintype "passive"))
      (node (ref "R30") (pin "1") (pinfunction "1_1") (pintype "passive"))
    )
    (net (code "42") (name "Net-(T1A-G)") (class "Default")
      (node (ref "R31") (pin "2") (pinfunction "2_2") (pintype "passive"))
      (node (ref "T1") (pin "2") (pinfunction "G_2") (pintype "passive"))
    )
    (net (code "43") (name "Net-(T1B-G)") (class "Default")
      (node (ref "R32") (pin "2") (pinfunction "2_2") (pintype "passive"))
      (node (ref "T1") (pin "4") (pinfunction "G_4") (pintype "passive"))
    )
    (net (code "44") (name "PDI_DATA") (class "Default")
      (node (ref "PDI") (pin "1") (pinfunction "1_1") (pintype "passive"))
      (node (ref "U1") (pin "56") (pinfunction "PDI_DATA_56") (pintype "bidirectional"))
    )
    (net (code "45") (name "RESET_PDI_CLK") (class "Default")
      (node (ref "PDI") (pin "5") (pinfunction "5_5") (pintype "passive"))
      (node (ref "U1") (pin "57") (pinfunction "/RESET_PDI_CLK_57") (pintype "bidirectional"))
    )
    (net (code "46") (name "RX") (class "Default")
      (node (ref "Q11") (pin "3") (pinfunction "D_3") (pintype "passive"))
      (node (ref "R27") (pin "2") (pinfunction "2_2") (pintype "passive"))
      (node (ref "U1") (pin "28") (pinfunction "PD2(OC0C/RXD0)_28") (pintype "bidirectional"))
    )
    (net (code "47") (name "RX_ATXMEGA") (class "Default")
      (node (ref "Q11") (pin "2") (pinfunction "S_2") (pintype "passive"))
      (node (ref "R26") (pin "2") (pinfunction "2_2") (pintype "passive"))
      (node (ref "RJ45_COMM") (pin "4") (pinfunction "4_4") (pintype "passive"))
    )
    (net (code "48") (name "S0") (class "Default")
      (node (ref "U1") (pin "23") (pinfunction "PC7(OC0DH/CKOUT/EVO/TXD1/SCK)_23") (pintype "bidirectional"))
      (node (ref "U9") (pin "10") (pinfunction "S0_10") (pintype "input"))
    )
    (net (code "49") (name "S1") (class "Default")
      (node (ref "U1") (pin "22") (pinfunction "PC6(OC0DL/RXD1/MISO)_22") (pintype "bidirectional"))
      (node (ref "U9") (pin "11") (pinfunction "S1_11") (pintype "input"))
    )
    (net (code "50") (name "S2") (class "Default")
      (node (ref "U1") (pin "21") (pinfunction "PC5(OC1B/OC0CH/XCK1/MOSI)_21") (pintype "bidirectional"))
      (node (ref "U9") (pin "14") (pinfunction "S2_14") (pintype "input"))
    )
    (net (code "51") (name "S3") (class "Default")
      (node (ref "U1") (pin "20") (pinfunction "PC4(AC1A/OC0CL/SS)_20") (pintype "bidirectional"))
      (node (ref "U9") (pin "13") (pinfunction "S3_13") (pintype "input"))
    )
    (net (code "52") (name "TEMP_1") (class "Default")
      (node (ref "R23") (pin "2") (pinfunction "2_2") (pintype "passive"))
      (node (ref "TEMP_1") (pin "P2") (pinfunction "2_P2") (pintype "bidirectional"))
      (node (ref "U1") (pin "32") (pinfunction "PD6(RXD1/MISO)_32") (pintype "bidirectional"))
    )
    (net (code "53") (name "TEMP_2") (class "Default")
      (node (ref "R24") (pin "2") (pinfunction "2_2") (pintype "passive"))
      (node (ref "TEMP_2") (pin "P2") (pinfunction "2_P2") (pintype "bidirectional"))
      (node (ref "U1") (pin "31") (pinfunction "PD5(OC1B/XCK1/MOSI)_31") (pintype "bidirectional"))
    )
    (net (code "54") (name "TEMP_3") (class "Default")
      (node (ref "R25") (pin "2") (pinfunction "2_2") (pintype "passive"))
      (node (ref "TEMP_3") (pin "P2") (pinfunction "2_P2") (pintype "bidirectional"))
      (node (ref "U1") (pin "30") (pinfunction "PD4(OC1A/SS)_30") (pintype "bidirectional"))
    )
    (net (code "55") (name "TRIGGER_1") (class "Default")
      (node (ref "Q10") (pin "3") (pinfunction "D_3") (pintype "passive"))
      (node (ref "R20") (pin "2") (pinfunction "2_2") (pintype "passive"))
      (node (ref "RJ45_WHITE") (pin "3") (pinfunction "3_3") (pintype "passive"))
    )
    (net (code "56") (name "TRIGGER_2") (class "Default")
      (node (ref "Q9") (pin "3") (pinfunction "D_3") (pintype "passive"))
      (node (ref "R18") (pin "2") (pinfunction "2_2") (pintype "passive"))
      (node (ref "RJ45_WHITE") (pin "4") (pinfunction "4_4") (pintype "passive"))
    )
    (net (code "57") (name "TX") (class "Default")
      (node (ref "Q12") (pin "2") (pinfunction "S_2") (pintype "passive"))
      (node (ref "R28") (pin "2") (pinfunction "2_2") (pintype "passive"))
      (node (ref "U1") (pin "29") (pinfunction "PD3(OX0D/TXD0)_29") (pintype "bidirectional"))
    )
    (net (code "58") (name "TX_ATXMEGA") (class "Default")
      (node (ref "Q12") (pin "3") (pinfunction "D_3") (pintype "passive"))
      (node (ref "R29") (pin "2") (pinfunction "2_2") (pintype "passive"))
      (node (ref "RJ45_COMM") (pin "6") (pinfunction "6_6") (pintype "passive"))
    )
    (net (code "59") (name "ULTRA1") (class "Default")
      (node (ref "U6") (pin "1") (pinfunction "A1_1") (pintype "bidirectional"))
      (node (ref "U9") (pin "9") (pinfunction "CHAN0_9") (pintype "bidirectional"))
    )
    (net (code "60") (name "ULTRA2") (class "Default")
      (node (ref "U6") (pin "3") (pinfunction "A2_3") (pintype "bidirectional"))
      (node (ref "U9") (pin "8") (pinfunction "CHAN1_8") (pintype "bidirectional"))
    )
    (net (code "61") (name "ULTRA3") (class "Default")
      (node (ref "U6") (pin "4") (pinfunction "A3_4") (pintype "bidirectional"))
      (node (ref "U9") (pin "7") (pinfunction "CHAN2_7") (pintype "bidirectional"))
    )
    (net (code "62") (name "ULTRA4") (class "Default")
      (node (ref "U6") (pin "5") (pinfunction "A4_5") (pintype "bidirectional"))
      (node (ref "U9") (pin "6") (pinfunction "CHAN3_6") (pintype "bidirectional"))
    )
    (net (code "63") (name "ULTRA5") (class "Default")
      (node (ref "U6") (pin "6") (pinfunction "A5_6") (pintype "bidirectional"))
      (node (ref "U9") (pin "5") (pinfunction "CHAN4_5") (pintype "bidirectional"))
    )
    (net (code "64") (name "ULTRA6") (class "Default")
      (node (ref "U6") (pin "7") (pinfunction "A6_7") (pintype "bidirectional"))
      (node (ref "U9") (pin "4") (pinfunction "CHAN5_4") (pintype "bidirectional"))
    )
    (net (code "65") (name "ULTRA7") (class "Default")
      (node (ref "U6") (pin "8") (pinfunction "A7_8") (pintype "bidirectional"))
      (node (ref "U9") (pin "3") (pinfunction "CHAN6_3") (pintype "bidirectional"))
    )
    (net (code "66") (name "ULTRA8") (class "Default")
      (node (ref "U6") (pin "9") (pinfunction "A8_9") (pintype "bidirectional"))
      (node (ref "U9") (pin "2") (pinfunction "CHAN7_2") (pintype "bidirectional"))
    )
    (net (code "67") (name "ULTRA9") (class "Default")
      (node (ref "U7") (pin "1") (pinfunction "A1_1") (pintype "bidirectional"))
      (node (ref "U9") (pin "23") (pinfunction "CHAN8_23") (pintype "bidirectional"))
    )
    (net (code "68") (name "ULTRA10") (class "Default")
      (node (ref "U7") (pin "3") (pinfunction "A2_3") (pintype "bidirectional"))
      (node (ref "U9") (pin "22") (pinfunction "CHAN9_22") (pintype "bidirectional"))
    )
    (net (code "69") (name "ULTRA11") (class "Default")
      (node (ref "U7") (pin "4") (pinfunction "A3_4") (pintype "bidirectional"))
      (node (ref "U9") (pin "21") (pinfunction "CHAN10_21") (pintype "bidirectional"))
    )
    (net (code "70") (name "ULTRA12") (class "Default")
      (node (ref "U7") (pin "5") (pinfunction "A4_5") (pintype "bidirectional"))
      (node (ref "U9") (pin "20") (pinfunction "CHAN11_20") (pintype "bidirectional"))
    )
    (net (code "71") (name "ULTRA13") (class "Default")
      (node (ref "U7") (pin "6") (pinfunction "A5_6") (pintype "bidirectional"))
      (node (ref "U9") (pin "19") (pinfunction "CHAN12_19") (pintype "bidirectional"))
    )
    (net (code "72") (name "ULTRA14") (class "Default")
      (node (ref "U7") (pin "7") (pinfunction "A6_7") (pintype "bidirectional"))
      (node (ref "U9") (pin "18") (pinfunction "CHAN13_18") (pintype "bidirectional"))
    )
    (net (code "73") (name "ULTRA15") (class "Default")
      (node (ref "U7") (pin "8") (pinfunction "A7_8") (pintype "bidirectional"))
      (node (ref "U9") (pin "17") (pinfunction "CHAN14_17") (pintype "bidirectional"))
    )
    (net (code "74") (name "ULTRA16") (class "Default")
      (node (ref "U7") (pin "9") (pinfunction "A8_9") (pintype "bidirectional"))
      (node (ref "U9") (pin "16") (pinfunction "CHAN15_16") (pintype "bidirectional"))
    )
    (net (code "75") (name "ULTRAS1") (class "Default")
      (node (ref "RJ45_RED") (pin "2") (pinfunction "2_2") (pintype "passive"))
      (node (ref "U6") (pin "20") (pinfunction "B1_20") (pintype "bidirectional"))
    )
    (net (code "76") (name "ULTRAS2") (class "Default")
      (node (ref "RJ45_RED") (pin "3") (pinfunction "3_3") (pintype "passive"))
      (node (ref "U6") (pin "18") (pinfunction "B2_18") (pintype "bidirectional"))
    )
    (net (code "77") (name "ULTRAS3") (class "Default")
      (node (ref "RJ45_RED") (pin "4") (pinfunction "4_4") (pintype "passive"))
      (node (ref "U6") (pin "17") (pinfunction "B3_17") (pintype "bidirectional"))
    )
    (net (code "78") (name "ULTRAS4") (class "Default")
      (node (ref "RJ45_RED") (pin "5") (pinfunction "5_5") (pintype "passive"))
      (node (ref "U6") (pin "16") (pinfunction "B4_16") (pintype "bidirectional"))
    )
    (net (code "79") (name "ULTRAS5") (class "Default")
      (node (ref "RJ45_RED") (pin "6") (pinfunction "6_6") (pintype "passive"))
      (node (ref "U6") (pin "15") (pinfunction "B5_15") (pintype "bidirectional"))
    )
    (net (code "80") (name "ULTRAS6") (class "Default")
      (node (ref "RJ45_RED") (pin "7") (pinfunction "7_7") (pintype "passive"))
      (node (ref "U6") (pin "14") (pinfunction "B6_14") (pintype "bidirectional"))
    )
    (net (code "81") (name "ULTRAS7") (class "Default")
      (node (ref "RJ45_WHITE") (pin "1") (pinfunction "1_1") (pintype "passive"))
      (node (ref "U6") (pin "13") (pinfunction "B7_13") (pintype "bidirectional"))
    )
    (net (code "82") (name "ULTRAS8") (class "Default")
      (node (ref "RJ45_WHITE") (pin "2") (pinfunction "2_2") (pintype "passive"))
      (node (ref "U6") (pin "12") (pinfunction "B8_12") (pintype "bidirectional"))
    )
    (net (code "83") (name "ULTRAS9") (class "Default")
      (node (ref "RJ45_WHITE") (pin "7") (pinfunction "7_7") (pintype "passive"))
      (node (ref "U7") (pin "20") (pinfunction "B1_20") (pintype "bidirectional"))
    )
    (net (code "84") (name "ULTRAS10") (class "Default")
      (node (ref "RJ45_WHITE") (pin "8") (pinfunction "8_8") (pintype "passive"))
      (node (ref "U7") (pin "18") (pinfunction "B2_18") (pintype "bidirectional"))
    )
    (net (code "85") (name "ULTRAS11") (class "Default")
      (node (ref "RJ45_BLUE") (pin "2") (pinfunction "2_2") (pintype "passive"))
      (node (ref "U7") (pin "17") (pinfunction "B3_17") (pintype "bidirectional"))
    )
    (net (code "86") (name "ULTRAS12") (class "Default")
      (node (ref "RJ45_BLUE") (pin "3") (pinfunction "3_3") (pintype "passive"))
      (node (ref "U7") (pin "16") (pinfunction "B4_16") (pintype "bidirectional"))
    )
    (net (code "87") (name "ULTRAS13") (class "Default")
      (node (ref "RJ45_BLUE") (pin "4") (pinfunction "4_4") (pintype "passive"))
      (node (ref "U7") (pin "15") (pinfunction "B5_15") (pintype "bidirectional"))
    )
    (net (code "88") (name "ULTRAS14") (class "Default")
      (node (ref "RJ45_BLUE") (pin "5") (pinfunction "5_5") (pintype "passive"))
      (node (ref "U7") (pin "14") (pinfunction "B6_14") (pintype "bidirectional"))
    )
    (net (code "89") (name "ULTRAS15") (class "Default")
      (node (ref "RJ45_BLUE") (pin "6") (pinfunction "6_6") (pintype "passive"))
      (node (ref "U7") (pin "13") (pinfunction "B7_13") (pintype "bidirectional"))
    )
    (net (code "90") (name "ULTRAS16") (class "Default")
      (node (ref "RJ45_BLUE") (pin "7") (pinfunction "7_7") (pintype "passive"))
      (node (ref "U7") (pin "12") (pinfunction "B8_12") (pintype "bidirectional"))
    )
    (net (code "91") (name "ULTRA_COM") (class "Default")
      (node (ref "U1") (pin "26") (pinfunction "PD0(OC0A)_26") (pintype "bidirectional"))
      (node (ref "U9") (pin "1") (pinfunction "COM_1") (pintype "bidirectional"))
    )
    (net (code "92") (name "ULTRA_TRIGGER_1") (class "Default")
      (node (ref "Q10") (pin "2") (pinfunction "S_2") (pintype "passive"))
      (node (ref "R19") (pin "2") (pinfunction "2_2") (pintype "passive"))
      (node (ref "U1") (pin "19") (pinfunction "PC3(OC0D/OX0BH/TXD0)_19") (pintype "bidirectional"))
    )
    (net (code "93") (name "ULTRA_TRIGGER_2") (class "Default")
      (node (ref "Q9") (pin "2") (pinfunction "S_2") (pintype "passive"))
      (node (ref "R17") (pin "2") (pinfunction "2_2") (pintype "passive"))
      (node (ref "U1") (pin "18") (pinfunction "PC2(OC0C/OC0BL/RXD0)_18") (pintype "bidirectional"))
    )
    (net (code "94") (name "VCC") (class "Default")
      (node (ref "C10") (pin "1") (pinfunction "1_1") (pintype "passive"))
      (node (ref "C11") (pin "1") (pinfunction "1_1") (pintype "passive"))
      (node (ref "C14") (pin "1") (pinfunction "1_1") (pintype "passive"))
      (node (ref "C15") (pin "1") (pinfunction "1_1") (pintype "passive"))
      (node (ref "C4") (pin "+") (pinfunction "+_+") (pintype "passive"))
      (node (ref "C5") (pin "+") (pinfunction "+_+") (pintype "passive"))
      (node (ref "C9") (pin "1") (pinfunction "1_1") (pintype "passive"))
      (node (ref "PDI") (pin "2") (pinfunction "2_2") (pintype "passive"))
      (node (ref "Q1") (pin "1") (pinfunction "G_1") (pintype "passive"))
      (node (ref "Q10") (pin "1") (pinfunction "G_1") (pintype "passive"))
      (node (ref "Q12") (pin "1") (pinfunction "G_1") (pintype "passive"))
      (node (ref "Q2") (pin "1") (pinfunction "G_1") (pintype "passive"))
      (node (ref "Q3") (pin "1") (pinfunction "G_1") (pintype "passive"))
      (node (ref "Q4") (pin "1") (pinfunction "G_1") (pintype "passive"))
      (node (ref "Q5") (pin "1") (pinfunction "G_1") (pintype "passive"))
      (node (ref "Q6") (pin "1") (pinfunction "G_1") (pintype "passive"))
      (node (ref "Q7") (pin "1") (pinfunction "G_1") (pintype "passive"))
      (node (ref "Q8") (pin "1") (pinfunction "G_1") (pintype "passive"))
      (node (ref "Q9") (pin "1") (pinfunction "G_1") (pintype "passive"))
      (node (ref "R1") (pin "1") (pinfunction "1_1") (pintype "passive"))
      (node (ref "R11") (pin "1") (pinfunction "1_1") (pintype "passive"))
      (node (ref "R13") (pin "1") (pinfunction "1_1") (pintype "passive"))
      (node (ref "R15") (pin "1") (pinfunction "1_1") (pintype "passive"))
      (node (ref "R17") (pin "1") (pinfunction "1_1") (pintype "passive"))
      (node (ref "R19") (pin "1") (pinfunction "1_1") (pintype "passive"))
      (node (ref "R2") (pin "1") (pinfunction "1_1") (pintype "passive"))
      (node (ref "R23") (pin "1") (pinfunction "1_1") (pintype "passive"))
      (node (ref "R24") (pin "1") (pinfunction "1_1") (pintype "passive"))
      (node (ref "R25") (pin "1") (pinfunction "1_1") (pintype "passive"))
      (node (ref "R27") (pin "1") (pinfunction "1_1") (pintype "passive"))
      (node (ref "R28") (pin "1") (pinfunction "1_1") (pintype "passive"))
      (node (ref "R4") (pin "1") (pinfunction "1_1") (pintype "passive"))
      (node (ref "R7") (pin "1") (pinfunction "1_1") (pintype "passive"))
      (node (ref "R9") (pin "1") (pinfunction "1_1") (pintype "passive"))
      (node (ref "RJ45_COMM") (pin "8") (pinfunction "8_8") (pintype "passive"))
      (node (ref "SENSOR1") (pin "3") (pinfunction "S_3") (pintype "passive"))
      (node (ref "SENSOR2") (pin "3") (pinfunction "S_3") (pintype "passive"))
      (node (ref "SENSOR3") (pin "3") (pinfunction "S_3") (pintype "passive"))
      (node (ref "SENSOR4") (pin "3") (pinfunction "S_3") (pintype "passive"))
      (node (ref "SENSOR5") (pin "3") (pinfunction "S_3") (pintype "passive"))
      (node (ref "SENSOR6") (pin "3") (pinfunction "S_3") (pintype "passive"))
      (node (ref "SENSOR7") (pin "3") (pinfunction "S_3") (pintype "passive"))
      (node (ref "SENSOR8") (pin "3") (pinfunction "S_3") (pintype "passive"))
      (node (ref "TEMP_1") (pin "P1") (pinfunction "1_P1") (pintype "bidirectional"))
      (node (ref "TEMP_2") (pin "P1") (pinfunction "1_P1") (pintype "bidirectional"))
      (node (ref "TEMP_3") (pin "P1") (pinfunction "1_P1") (pintype "bidirectional"))
      (node (ref "U1") (pin "15") (pinfunction "VCC1_15") (pintype "bidirectional"))
      (node (ref "U1") (pin "25") (pinfunction "VCC2_25") (pintype "bidirectional"))
      (node (ref "U1") (pin "35") (pinfunction "VCC3_35") (pintype "bidirectional"))
      (node (ref "U1") (pin "45") (pinfunction "VCC4_45") (pintype "bidirectional"))
      (node (ref "U1") (pin "53") (pinfunction "VCC5_53") (pintype "bidirectional"))
      (node (ref "U1") (pin "61") (pinfunction "AVCC_61") (pintype "bidirectional"))
      (node (ref "U3") (pin "2") (pinfunction "OUTPUT_2_2") (pintype "output"))
      (node (ref "U3") (pin "4") (pinfunction "OUTPUT_4") (pintype "output"))
      (node (ref "U4") (pin "16") (pinfunction "VDD_16") (pintype "input"))
      (node (ref "U6") (pin "10") (pinfunction "OE_10") (pintype "input"))
      (node (ref "U6") (pin "2") (pinfunction "VCCA_2") (pintype "power_in"))
      (node (ref "U7") (pin "10") (pinfunction "OE_10") (pintype "input"))
      (node (ref "U7") (pin "2") (pinfunction "VCCA_2") (pintype "power_in"))
      (node (ref "U9") (pin "24") (pinfunction "VCC_24") (pintype "bidirectional"))
    )
    (net (code "95") (name "unconnected-(PDI-Pad3)") (class "Default")
      (node (ref "PDI") (pin "3") (pinfunction "3_3") (pintype "passive"))
    )
    (net (code "96") (name "unconnected-(PDI-Pad4)") (class "Default")
      (node (ref "PDI") (pin "4") (pinfunction "4_4") (pintype "passive"))
    )
    (net (code "97") (name "unconnected-(U1-PB0(ADC0{slash}AC0{slash}AREF)-Pad6)") (class "Default")
      (node (ref "U1") (pin "6") (pinfunction "PB0(ADC0/AC0/AREF)_6") (pintype "bidirectional"))
    )
    (net (code "98") (name "unconnected-(U1-PB1(ADC1{slash}AC1)-Pad7)") (class "Default")
      (node (ref "U1") (pin "7") (pinfunction "PB1(ADC1/AC1)_7") (pintype "bidirectional"))
    )
    (net (code "99") (name "unconnected-(U1-PB2(ADC2{slash}AC2{slash}DAC0)-Pad8)") (class "Default")
      (node (ref "U1") (pin "8") (pinfunction "PB2(ADC2/AC2/DAC0)_8") (pintype "bidirectional"))
    )
    (net (code "100") (name "unconnected-(U1-PB3(ADC3{slash}AC3{slash}DAC1)-Pad9)") (class "Default")
      (node (ref "U1") (pin "9") (pinfunction "PB3(ADC3/AC3/DAC1)_9") (pintype "bidirectional"))
    )
    (net (code "101") (name "unconnected-(U1-PB4(ADC4{slash}AC4{slash}TMS)-Pad10)") (class "Default")
      (node (ref "U1") (pin "10") (pinfunction "PB4(ADC4/AC4/TMS)_10") (pintype "bidirectional"))
    )
    (net (code "102") (name "unconnected-(U1-PB5(ADC5{slash}AC5{slash}TDI)-Pad11)") (class "Default")
      (node (ref "U1") (pin "11") (pinfunction "PB5(ADC5/AC5/TDI)_11") (pintype "bidirectional"))
    )
    (net (code "103") (name "unconnected-(U1-PB6(ADC6{slash}AC6{slash}TCK)-Pad12)") (class "Default")
      (node (ref "U1") (pin "12") (pinfunction "PB6(ADC6/AC6/TCK)_12") (pintype "bidirectional"))
    )
    (net (code "104") (name "unconnected-(U1-PB7(ADC7{slash}AC7{slash}AC0OUT{slash}TDO)-Pad13)") (class "Default")
      (node (ref "U1") (pin "13") (pinfunction "PB7(ADC7/AC7/AC0OUT/TDO)_13") (pintype "bidirectional"))
    )
    (net (code "105") (name "unconnected-(U1-PD7(CKOUT{slash}EVO{slash}TXD1{slash}SCK)-Pad33)") (class "Default")
      (node (ref "U1") (pin "33") (pinfunction "PD7(CKOUT/EVO/TXD1/SCK)_33") (pintype "bidirectional"))
    )
    (net (code "106") (name "unconnected-(U1-PE0(OC0A{slash}SDA)-Pad36)") (class "Default")
      (node (ref "U1") (pin "36") (pinfunction "PE0(OC0A/SDA)_36") (pintype "bidirectional"))
    )
    (net (code "107") (name "unconnected-(U1-PE1(OC0B{slash}XCK0{slash}SCL)-Pad37)") (class "Default")
      (node (ref "U1") (pin "37") (pinfunction "PE1(OC0B/XCK0/SCL)_37") (pintype "bidirectional"))
    )
    (net (code "108") (name "unconnected-(U1-PE2(OC0C{slash}RXD0)-Pad38)") (class "Default")
      (node (ref "U1") (pin "38") (pinfunction "PE2(OC0C/RXD0)_38") (pintype "bidirectional"))
    )
    (net (code "109") (name "unconnected-(U1-PE3(OC0D{slash}TXD0)-Pad39)") (class "Default")
      (node (ref "U1") (pin "39") (pinfunction "PE3(OC0D/TXD0)_39") (pintype "bidirectional"))
    )
    (net (code "110") (name "unconnected-(U1-PE4(OC1A{slash}SS)-Pad40)") (class "Default")
      (node (ref "U1") (pin "40") (pinfunction "PE4(OC1A/SS)_40") (pintype "bidirectional"))
    )
    (net (code "111") (name "unconnected-(U1-PE5(OC1B{slash}XCK1{slash}MOSI)-Pad41)") (class "Default")
      (node (ref "U1") (pin "41") (pinfunction "PE5(OC1B/XCK1/MOSI)_41") (pintype "bidirectional"))
    )
    (net (code "112") (name "unconnected-(U1-PE6(TOSC2{slash}RXD1{slash}MISO)-Pad42)") (class "Default")
      (node (ref "U1") (pin "42") (pinfunction "PE6(TOSC2/RXD1/MISO)_42") (pintype "bidirectional"))
    )
    (net (code "113") (name "unconnected-(U1-PE7(TOSC1{slash}CKOUT{slash}EVO{slash}TXD1{slash}SCK)-Pad43)") (class "Default")
      (node (ref "U1") (pin "43") (pinfunction "PE7(TOSC1/CKOUT/EVO/TXD1/SCK)_43") (pintype "bidirectional"))
    )
    (net (code "114") (name "unconnected-(U1-PF5-Pad51)") (class "Default")
      (node (ref "U1") (pin "51") (pinfunction "PF5_51") (pintype "bidirectional"))
    )
    (net (code "115") (name "unconnected-(U1-PF7-Pad55)") (class "Default")
      (node (ref "U1") (pin "55") (pinfunction "PF7_55") (pintype "bidirectional"))
    )
    (net (code "116") (name "unconnected-(U1-PR0(XTAL2)-Pad58)") (class "Default")
      (node (ref "U1") (pin "58") (pinfunction "PR0(XTAL2)_58") (pintype "bidirectional"))
    )
    (net (code "117") (name "unconnected-(U1-PR1(XTAL1)-Pad59)") (class "Default")
      (node (ref "U1") (pin "59") (pinfunction "PR1(XTAL1)_59") (pintype "bidirectional"))
    )
  )
)
